# RF-PWR-001.net
KiCad netlist of a schematic drawn in EAGLE
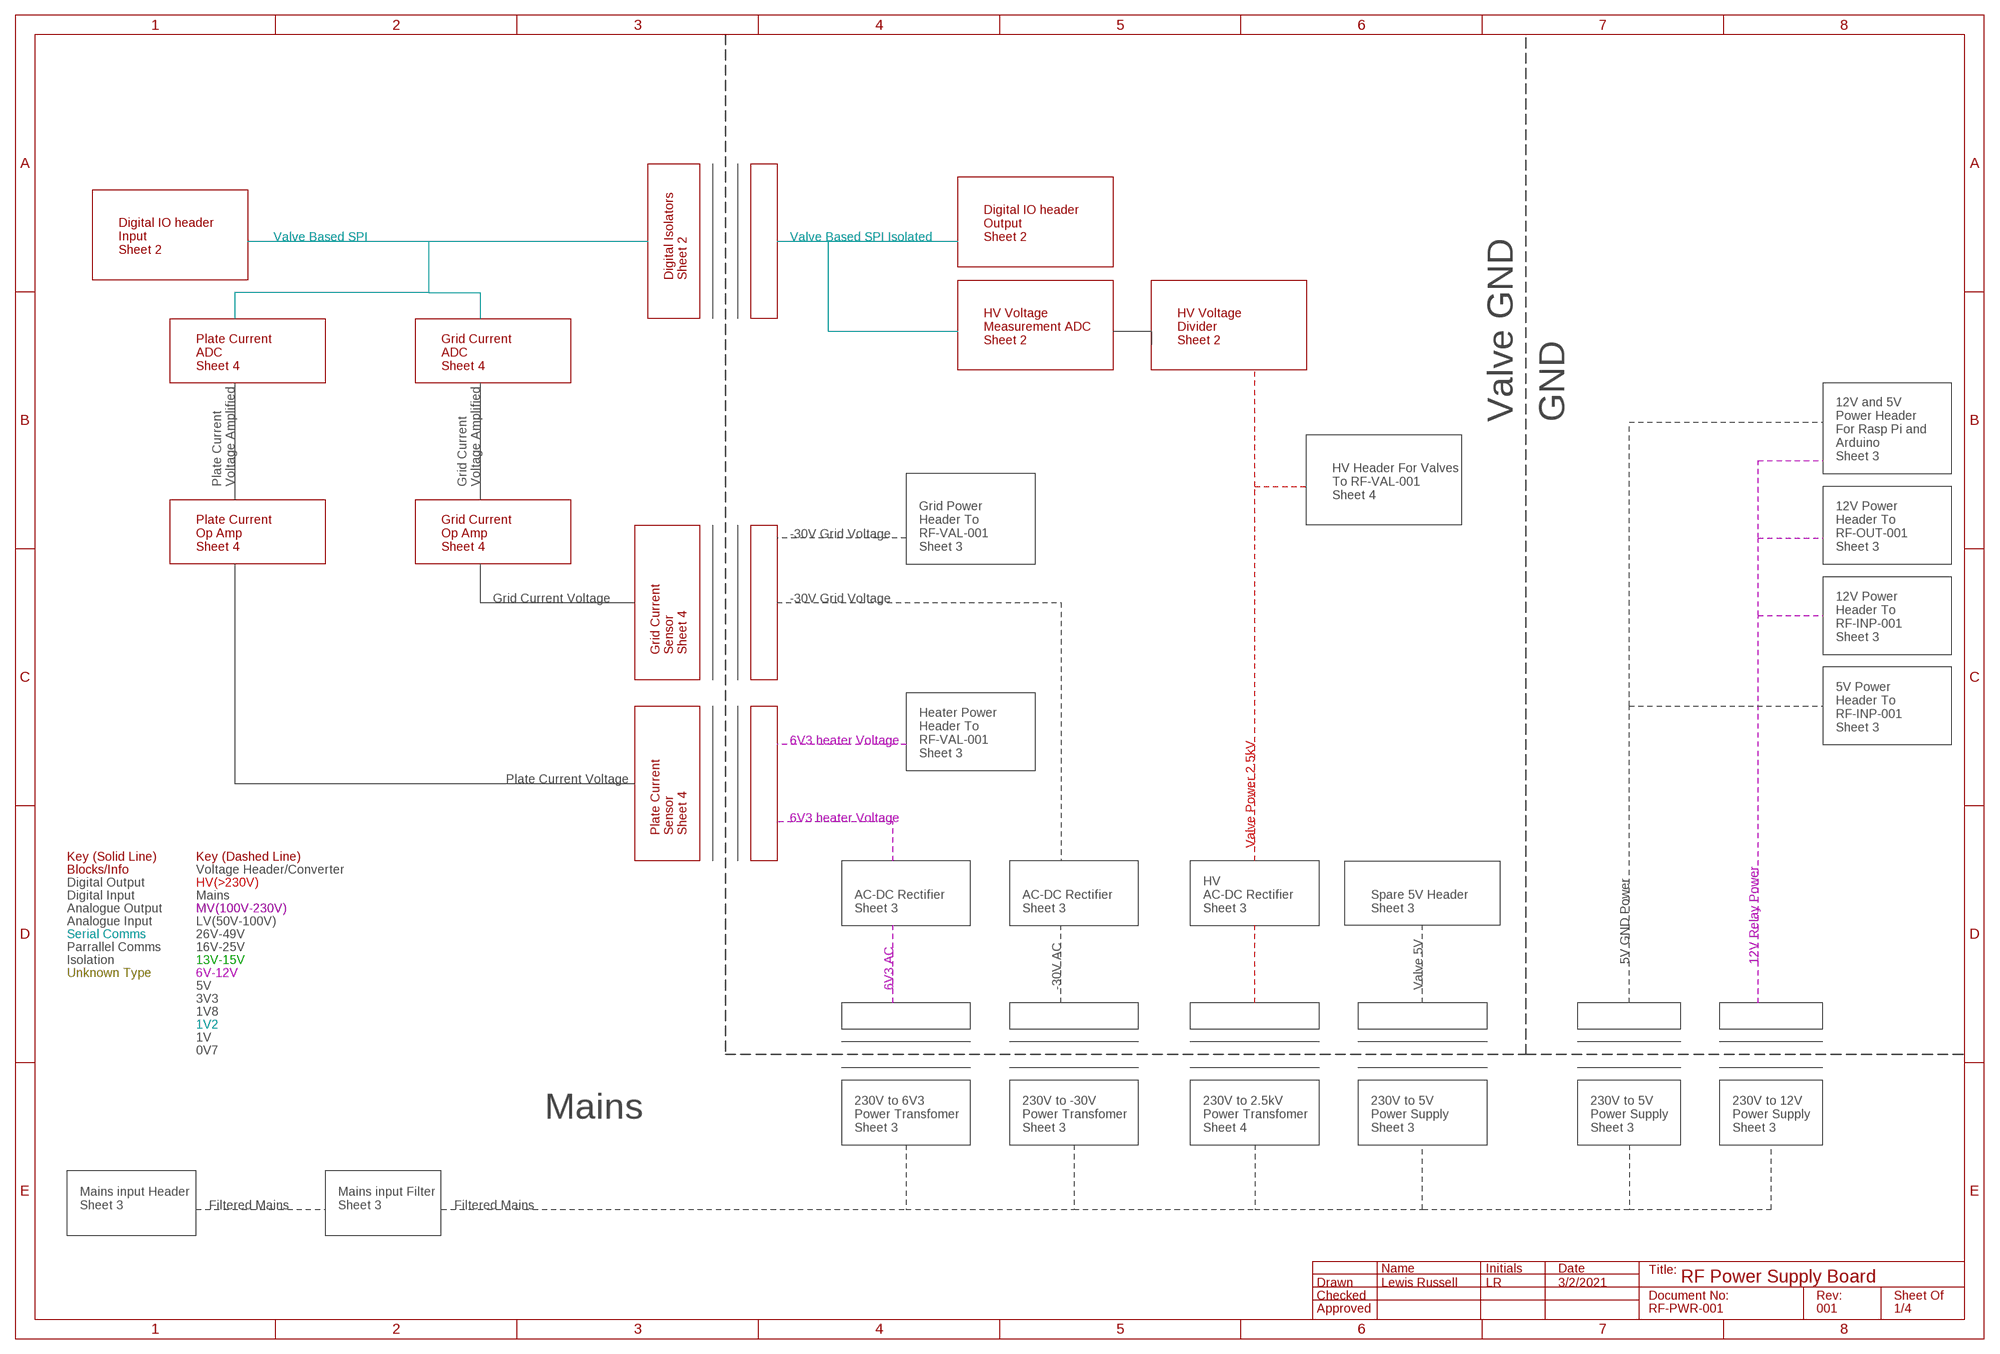
[diagram p0: schematic, sheet 1]
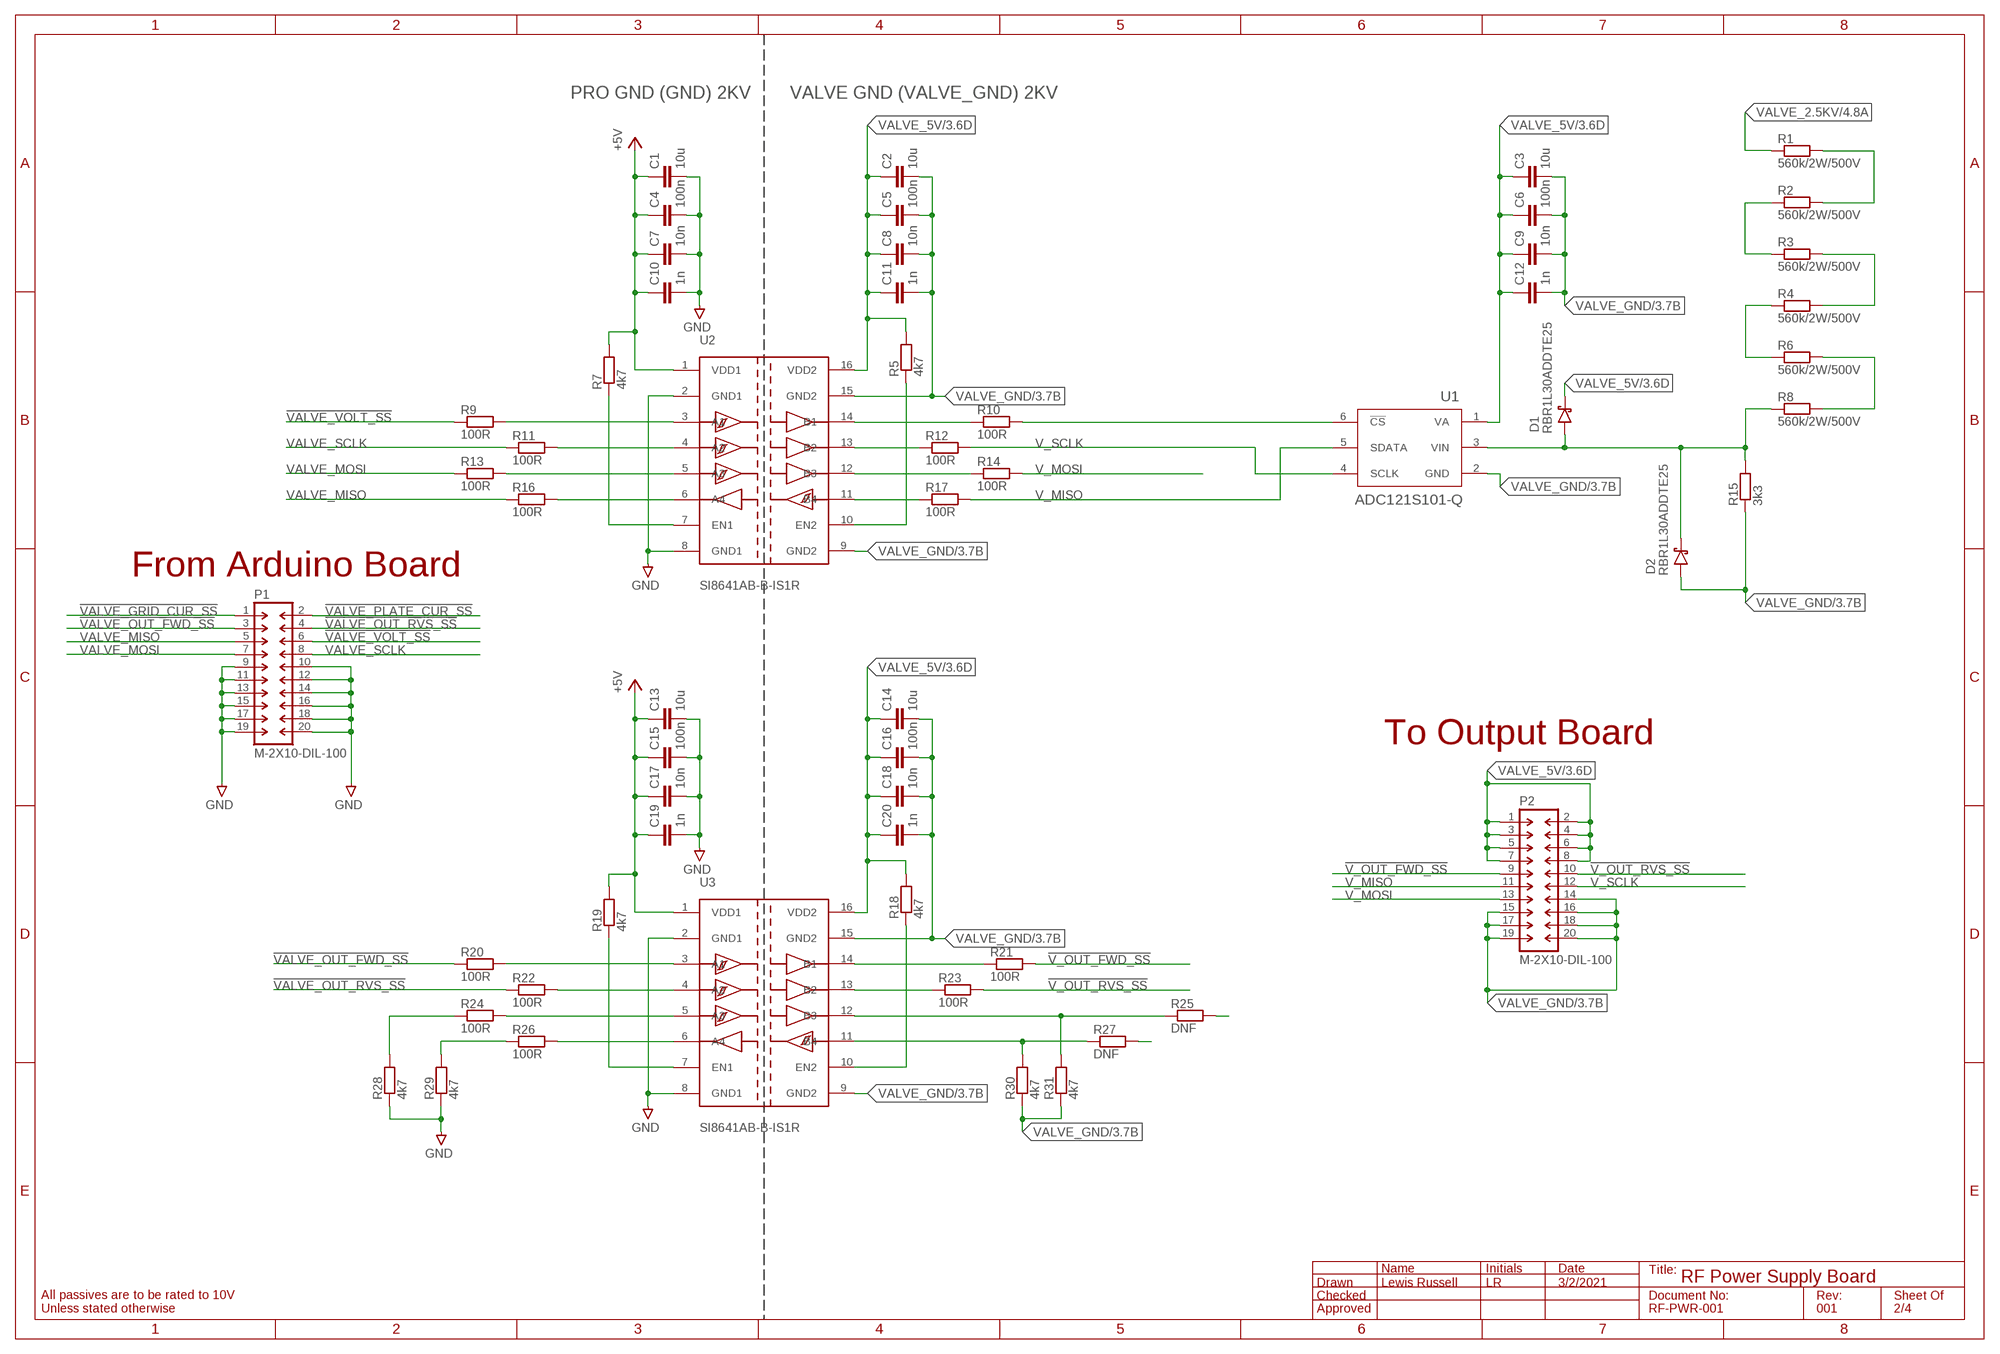
[diagram p1: schematic, sheet 2]
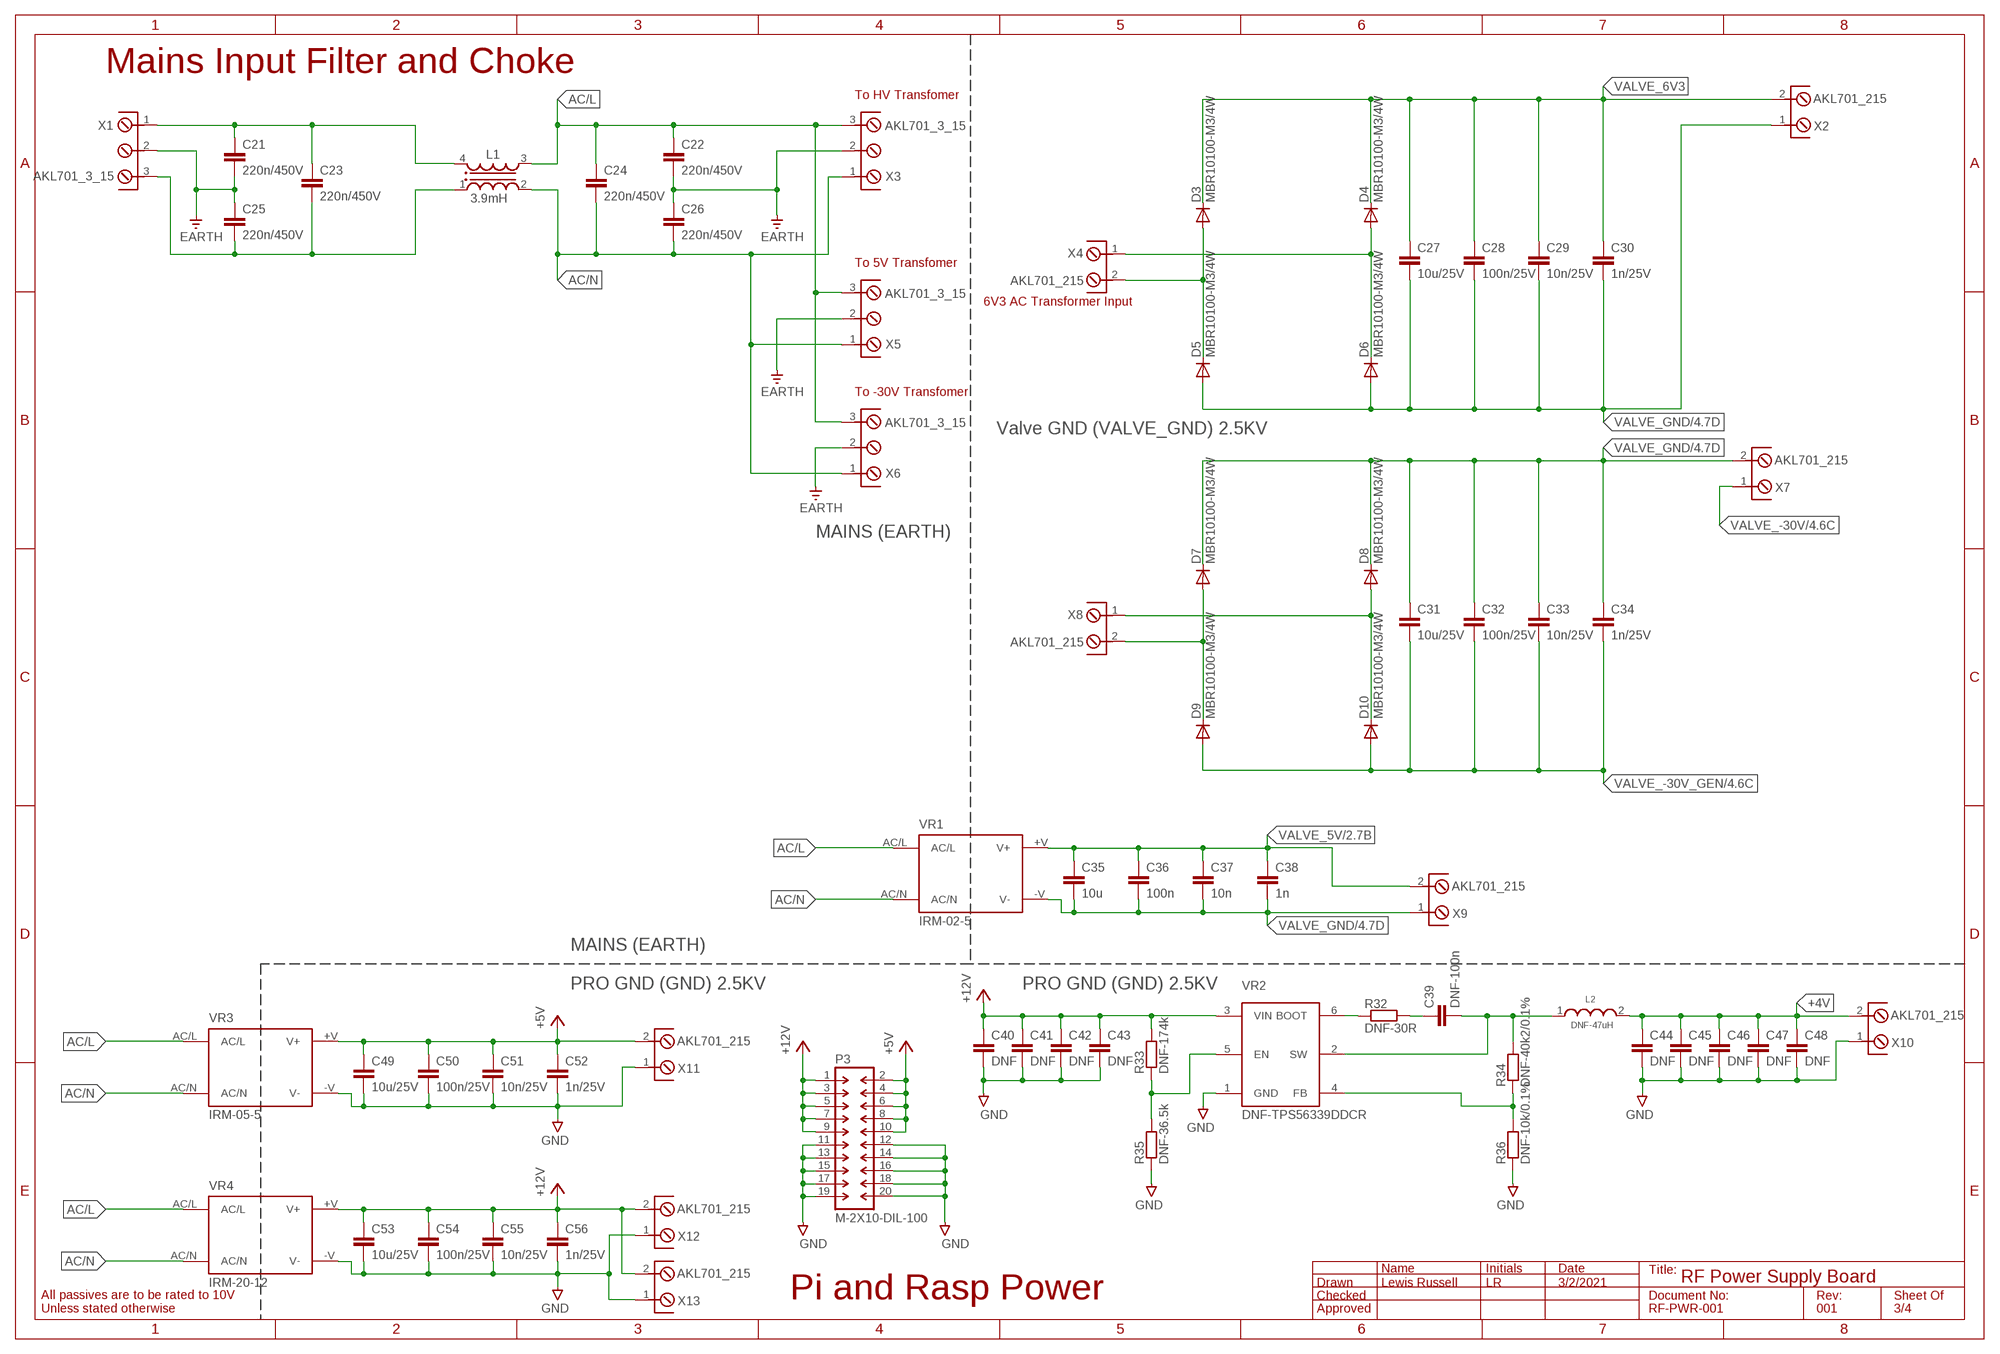
[diagram p2: schematic, sheet 3]
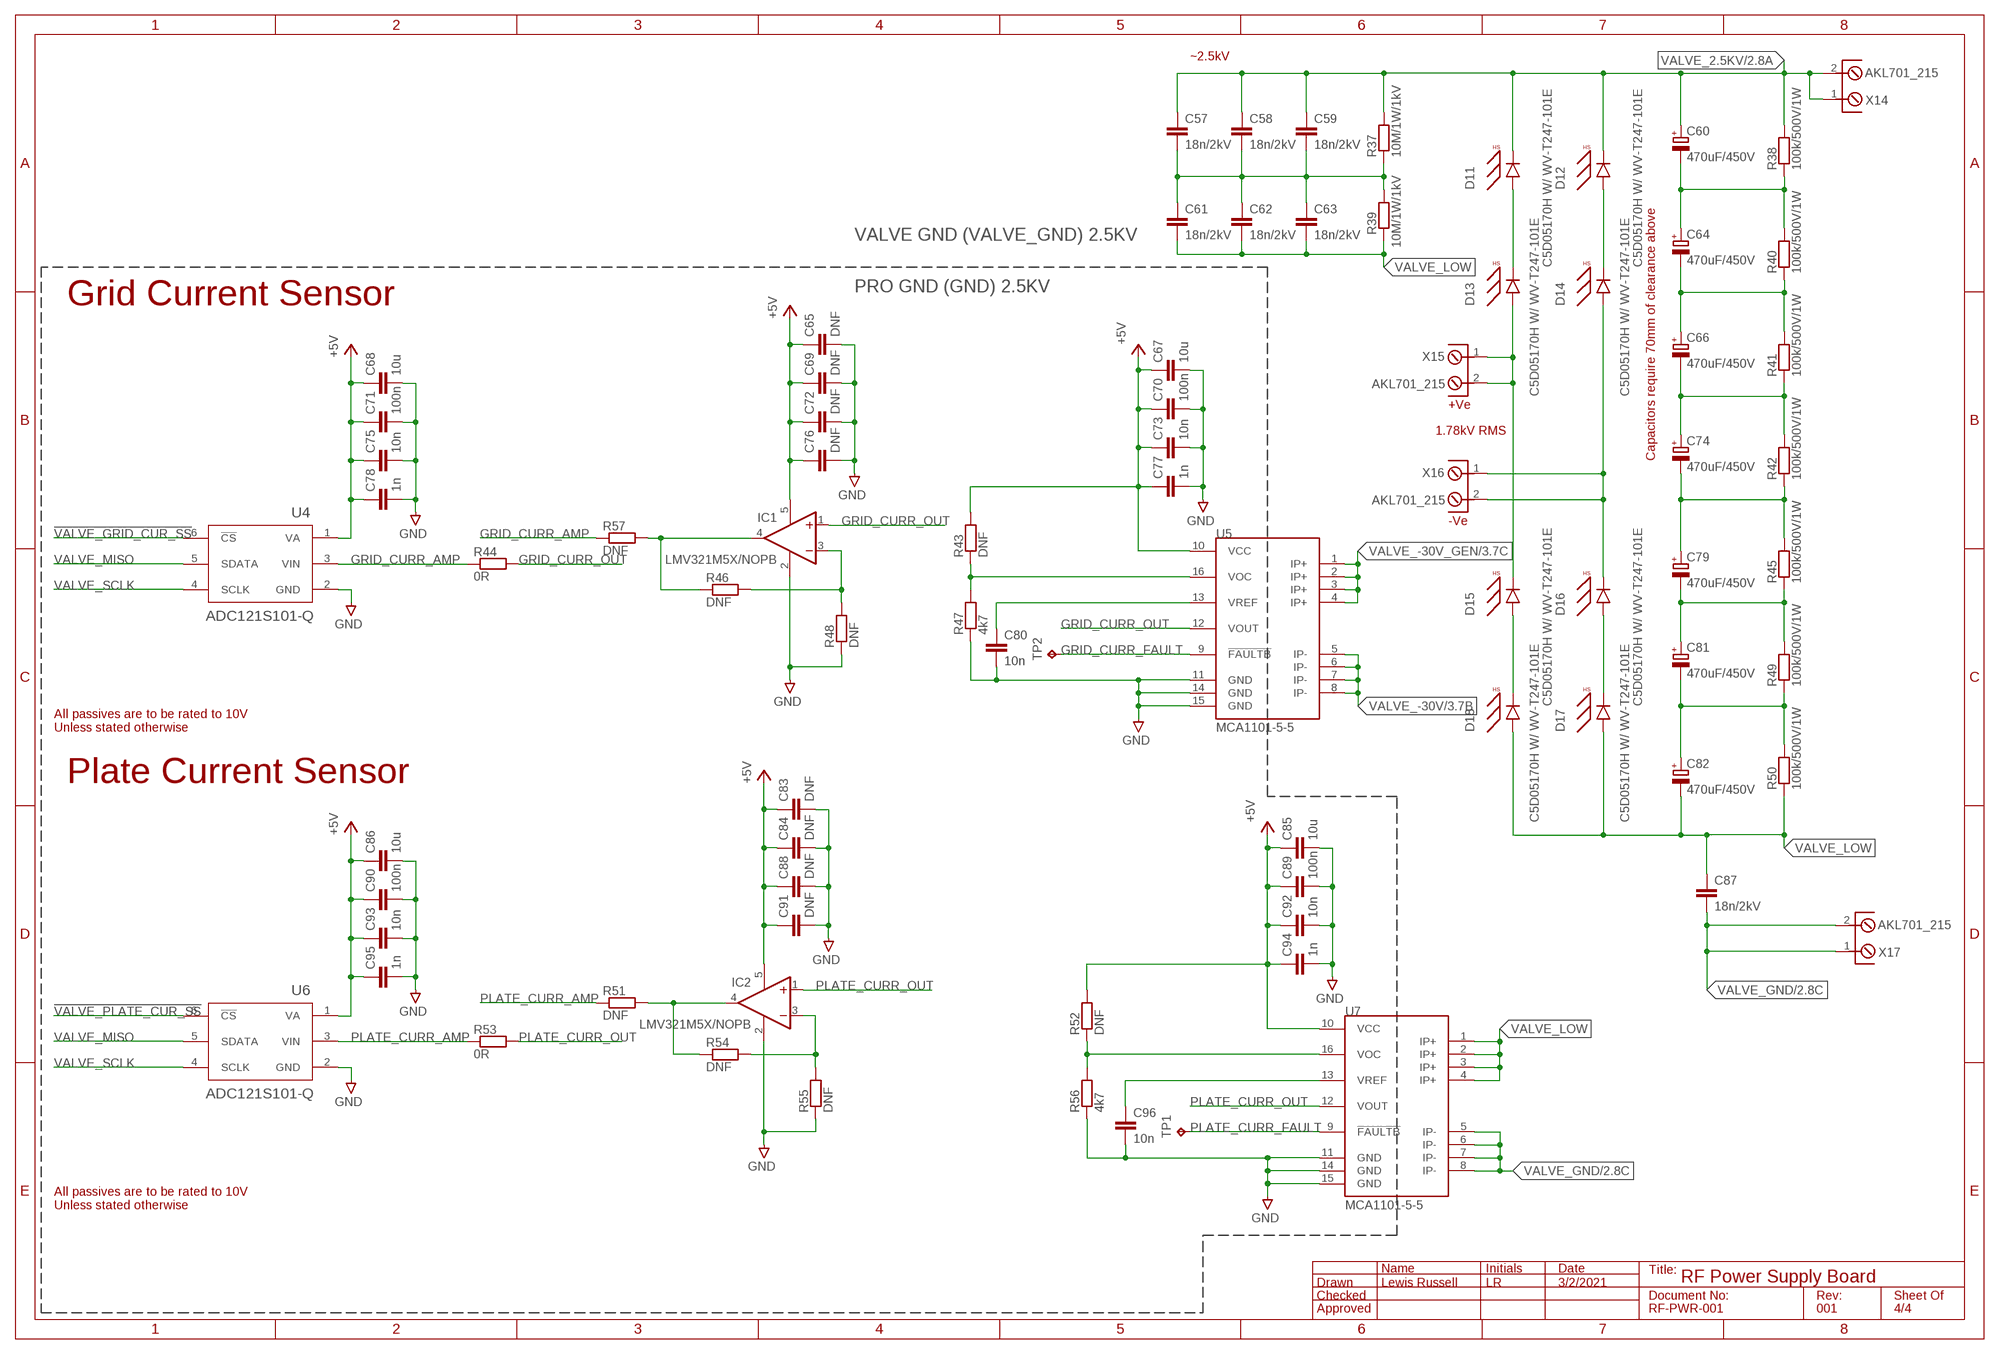
[diagram p3: schematic, sheet 4]

(export (version "E")
  (design (tool "Eeschema 10.0.6"))
  (components
    (comp (ref "C21")
      (value "220n/450V")
      (footprint "eagle-import:C1210")
      (libsource (lib "eagle-import") (part "C-EUC1210"))
    )
    (comp (ref "C22")
      (value "220n/450V")
      (footprint "eagle-import:C1210")
      (libsource (lib "eagle-import") (part "C-EUC1210"))
    )
    (comp (ref "C23")
      (value "220n/450V")
      (footprint "eagle-import:C1210")
      (libsource (lib "eagle-import") (part "C-EUC1210"))
    )
    (comp (ref "C24")
      (value "220n/450V")
      (footprint "eagle-import:C1210")
      (libsource (lib "eagle-import") (part "C-EUC1210"))
    )
    (comp (ref "C25")
      (value "220n/450V")
      (footprint "eagle-import:C1210")
      (libsource (lib "eagle-import") (part "C-EUC1210"))
    )
    (comp (ref "C26")
      (value "220n/450V")
      (footprint "eagle-import:C1210")
      (libsource (lib "eagle-import") (part "C-EUC1210"))
    )
    (comp (ref "C27")
      (value "10u/25V")
      (footprint "eagle-import:C0805")
      (libsource (lib "eagle-import") (part "C-EUC0805"))
    )
    (comp (ref "C28")
      (value "100n/25V")
      (footprint "eagle-import:C0603")
      (libsource (lib "eagle-import") (part "C-EUC0603"))
    )
    (comp (ref "C29")
      (value "10n/25V")
      (footprint "eagle-import:C0603")
      (libsource (lib "eagle-import") (part "C-EUC0603"))
    )
    (comp (ref "C30")
      (value "1n/25V")
      (footprint "eagle-import:C0603")
      (libsource (lib "eagle-import") (part "C-EUC0603"))
    )
    (comp (ref "C31")
      (value "10u/25V")
      (footprint "eagle-import:C0805")
      (libsource (lib "eagle-import") (part "C-EUC0805"))
    )
    (comp (ref "C32")
      (value "100n/25V")
      (footprint "eagle-import:C0603")
      (libsource (lib "eagle-import") (part "C-EUC0603"))
    )
    (comp (ref "C33")
      (value "10n/25V")
      (footprint "eagle-import:C0603")
      (libsource (lib "eagle-import") (part "C-EUC0603"))
    )
    (comp (ref "C34")
      (value "1n/25V")
      (footprint "eagle-import:C0603")
      (libsource (lib "eagle-import") (part "C-EUC0603"))
    )
    (comp (ref "C35")
      (value "10u")
      (footprint "eagle-import:C0805")
      (libsource (lib "eagle-import") (part "C-EUC0805"))
    )
    (comp (ref "C36")
      (value "100n")
      (footprint "eagle-import:C0603")
      (libsource (lib "eagle-import") (part "C-EUC0603"))
    )
    (comp (ref "C37")
      (value "10n")
      (footprint "eagle-import:C0603")
      (libsource (lib "eagle-import") (part "C-EUC0603"))
    )
    (comp (ref "C38")
      (value "1n")
      (footprint "eagle-import:C0603")
      (libsource (lib "eagle-import") (part "C-EUC0603"))
    )
    (comp (ref "C39")
      (value "DNF-100n")
      (footprint "eagle-import:C0603")
      (libsource (lib "eagle-import") (part "C-EUC0603"))
    )
    (comp (ref "C40")
      (value "DNF")
      (footprint "eagle-import:C0805")
      (libsource (lib "eagle-import") (part "C-EUC0805"))
    )
    (comp (ref "C41")
      (value "DNF")
      (footprint "eagle-import:C0603")
      (libsource (lib "eagle-import") (part "C-EUC0603"))
    )
    (comp (ref "C42")
      (value "DNF")
      (footprint "eagle-import:C0603")
      (libsource (lib "eagle-import") (part "C-EUC0603"))
    )
    (comp (ref "C43")
      (value "DNF")
      (footprint "eagle-import:C0603")
      (libsource (lib "eagle-import") (part "C-EUC0603"))
    )
    (comp (ref "C44")
      (value "DNF")
      (footprint "eagle-import:C1206")
      (libsource (lib "eagle-import") (part "C-EUC1206"))
    )
    (comp (ref "C45")
      (value "DNF")
      (footprint "eagle-import:C0805")
      (libsource (lib "eagle-import") (part "C-EUC0805"))
    )
    (comp (ref "C46")
      (value "DNF")
      (footprint "eagle-import:C0603")
      (libsource (lib "eagle-import") (part "C-EUC0603"))
    )
    (comp (ref "C47")
      (value "DNF")
      (footprint "eagle-import:C0603")
      (libsource (lib "eagle-import") (part "C-EUC0603"))
    )
    (comp (ref "C48")
      (value "DNF")
      (footprint "eagle-import:C0603")
      (libsource (lib "eagle-import") (part "C-EUC0603"))
    )
    (comp (ref "C49")
      (value "10u/25V")
      (footprint "eagle-import:C0805")
      (libsource (lib "eagle-import") (part "C-EUC0805"))
    )
    (comp (ref "C50")
      (value "100n/25V")
      (footprint "eagle-import:C0603")
      (libsource (lib "eagle-import") (part "C-EUC0603"))
    )
    (comp (ref "C51")
      (value "10n/25V")
      (footprint "eagle-import:C0603")
      (libsource (lib "eagle-import") (part "C-EUC0603"))
    )
    (comp (ref "C52")
      (value "1n/25V")
      (footprint "eagle-import:C0603")
      (libsource (lib "eagle-import") (part "C-EUC0603"))
    )
    (comp (ref "C53")
      (value "10u/25V")
      (footprint "eagle-import:C0805")
      (libsource (lib "eagle-import") (part "C-EUC0805"))
    )
    (comp (ref "C54")
      (value "100n/25V")
      (footprint "eagle-import:C0603")
      (libsource (lib "eagle-import") (part "C-EUC0603"))
    )
    (comp (ref "C55")
      (value "10n/25V")
      (footprint "eagle-import:C0603")
      (libsource (lib "eagle-import") (part "C-EUC0603"))
    )
    (comp (ref "C56")
      (value "1n/25V")
      (footprint "eagle-import:C0603")
      (libsource (lib "eagle-import") (part "C-EUC0603"))
    )
    (comp (ref "D3")
      (value "MBR10100-M3/4W")
      (footprint "eagle-import:TO220ACS")
      (libsource (lib "eagle-import") (part "DIODE-TO220V"))
    )
    (comp (ref "D4")
      (value "MBR10100-M3/4W")
      (footprint "eagle-import:TO220ACS")
      (libsource (lib "eagle-import") (part "DIODE-TO220V"))
    )
    (comp (ref "D5")
      (value "MBR10100-M3/4W")
      (footprint "eagle-import:TO220ACS")
      (libsource (lib "eagle-import") (part "DIODE-TO220V"))
    )
    (comp (ref "D6")
      (value "MBR10100-M3/4W")
      (footprint "eagle-import:TO220ACS")
      (libsource (lib "eagle-import") (part "DIODE-TO220V"))
    )
    (comp (ref "D7")
      (value "MBR10100-M3/4W")
      (footprint "eagle-import:TO220ACS")
      (libsource (lib "eagle-import") (part "DIODE-TO220V"))
    )
    (comp (ref "D8")
      (value "MBR10100-M3/4W")
      (footprint "eagle-import:TO220ACS")
      (libsource (lib "eagle-import") (part "DIODE-TO220V"))
    )
    (comp (ref "D9")
      (value "MBR10100-M3/4W")
      (footprint "eagle-import:TO220ACS")
      (libsource (lib "eagle-import") (part "DIODE-TO220V"))
    )
    (comp (ref "D10")
      (value "MBR10100-M3/4W")
      (footprint "eagle-import:TO220ACS")
      (libsource (lib "eagle-import") (part "DIODE-TO220V"))
    )
    (comp (ref "L1")
      (value "3.9mH")
      (footprint "eagle-import:WE-FCL_ET35")
      (libsource (lib "eagle-import") (part "WE-FCL_ET35_744866392"))
    )
    (comp (ref "L2")
      (value "DNF-47uH")
      (footprint "eagle-import:WE-HCF_2920_ROUND")
      (libsource (lib "eagle-import") (part "WE-HCF_2920_ROUND_74437529203470"))
    )
    (comp (ref "P3")
      (value "M-2X10-DIL-100")
      (footprint "eagle-import:DIL-100-2X10")
      (libsource (lib "eagle-import") (part "M-2X10-DIL-100"))
    )
    (comp (ref "R32")
      (value "DNF-30R")
      (footprint "eagle-import:R0603")
      (libsource (lib "eagle-import") (part "R-EUR0603"))
    )
    (comp (ref "R33")
      (value "DNF-174k")
      (footprint "eagle-import:R0603")
      (libsource (lib "eagle-import") (part "R-EUR0603"))
    )
    (comp (ref "R34")
      (value "DNF-40k2/0.1%")
      (footprint "eagle-import:R0603")
      (libsource (lib "eagle-import") (part "R-EUR0603"))
    )
    (comp (ref "R35")
      (value "DNF-36.5k")
      (footprint "eagle-import:R0603")
      (libsource (lib "eagle-import") (part "R-EUR0603"))
    )
    (comp (ref "R36")
      (value "DNF-10k/0.1%")
      (footprint "eagle-import:R0603")
      (libsource (lib "eagle-import") (part "R-EUR0603"))
    )
    (comp (ref "VR1")
      (value "IRM-02-5")
      (footprint "eagle-import:IRM_1-2_TH")
      (libsource (lib "eagle-import") (part "IRM-02-5"))
    )
    (comp (ref "VR2")
      (value "DNF-TPS56339DDCR")
      (footprint "eagle-import:SOT23-6")
      (libsource (lib "eagle-import") (part "TPS56339DDCR"))
    )
    (comp (ref "VR3")
      (value "IRM-05-5")
      (footprint "eagle-import:IRM_5-10_TH")
      (libsource (lib "eagle-import") (part "IRM-05-5"))
    )
    (comp (ref "VR4")
      (value "IRM-20-12")
      (footprint "eagle-import:IRM_15-20_TH")
      (libsource (lib "eagle-import") (part "IRM-20-12"))
    )
    (comp (ref "X1")
      (value "AKL701_3_15")
      (footprint "eagle-import:AKL701_3_15")
      (libsource (lib "eagle-import") (part "AKL701_3_15"))
    )
    (comp (ref "X2")
      (value "AKL701_215")
      (footprint "eagle-import:AKL701_2_15")
      (libsource (lib "eagle-import") (part "AKL701_215"))
    )
    (comp (ref "X3")
      (value "AKL701_3_15")
      (footprint "eagle-import:AKL701_3_15")
      (libsource (lib "eagle-import") (part "AKL701_3_15"))
    )
    (comp (ref "X4")
      (value "AKL701_215")
      (footprint "eagle-import:AKL701_2_15")
      (libsource (lib "eagle-import") (part "AKL701_215"))
    )
    (comp (ref "X5")
      (value "AKL701_3_15")
      (footprint "eagle-import:AKL701_3_15")
      (libsource (lib "eagle-import") (part "AKL701_3_15"))
    )
    (comp (ref "X6")
      (value "AKL701_3_15")
      (footprint "eagle-import:AKL701_3_15")
      (libsource (lib "eagle-import") (part "AKL701_3_15"))
    )
    (comp (ref "X7")
      (value "AKL701_215")
      (footprint "eagle-import:AKL701_2_15")
      (libsource (lib "eagle-import") (part "AKL701_215"))
    )
    (comp (ref "X8")
      (value "AKL701_215")
      (footprint "eagle-import:AKL701_2_15")
      (libsource (lib "eagle-import") (part "AKL701_215"))
    )
    (comp (ref "X9")
      (value "AKL701_215")
      (footprint "eagle-import:AKL701_2_15")
      (libsource (lib "eagle-import") (part "AKL701_215"))
    )
    (comp (ref "X10")
      (value "AKL701_215")
      (footprint "eagle-import:AKL701_2_15")
      (libsource (lib "eagle-import") (part "AKL701_215"))
    )
    (comp (ref "X11")
      (value "AKL701_215")
      (footprint "eagle-import:AKL701_2_15")
      (libsource (lib "eagle-import") (part "AKL701_215"))
    )
    (comp (ref "X12")
      (value "AKL701_215")
      (footprint "eagle-import:AKL701_2_15")
      (libsource (lib "eagle-import") (part "AKL701_215"))
    )
    (comp (ref "X13")
      (value "AKL701_215")
      (footprint "eagle-import:AKL701_2_15")
      (libsource (lib "eagle-import") (part "AKL701_215"))
    )
    (comp (ref "C57")
      (value "18n/2kV")
      (footprint "eagle-import:C050-075X075")
      (libsource (lib "eagle-import") (part "C-EU050-075X075"))
    )
    (comp (ref "C58")
      (value "18n/2kV")
      (footprint "eagle-import:C050-075X075")
      (libsource (lib "eagle-import") (part "C-EU050-075X075"))
    )
    (comp (ref "C59")
      (value "18n/2kV")
      (footprint "eagle-import:C050-075X075")
      (libsource (lib "eagle-import") (part "C-EU050-075X075"))
    )
    (comp (ref "C60")
      (value "470uF/450V")
      (footprint "eagle-import:STYLE_D(35MM)")
      (libsource (lib "eagle-import") (part "ALC10D-35MM"))
    )
    (comp (ref "C61")
      (value "18n/2kV")
      (footprint "eagle-import:C050-075X075")
      (libsource (lib "eagle-import") (part "C-EU050-075X075"))
    )
    (comp (ref "C62")
      (value "18n/2kV")
      (footprint "eagle-import:C050-075X075")
      (libsource (lib "eagle-import") (part "C-EU050-075X075"))
    )
    (comp (ref "C63")
      (value "18n/2kV")
      (footprint "eagle-import:C050-075X075")
      (libsource (lib "eagle-import") (part "C-EU050-075X075"))
    )
    (comp (ref "C64")
      (value "470uF/450V")
      (footprint "eagle-import:STYLE_D(35MM)")
      (libsource (lib "eagle-import") (part "ALC10D-35MM"))
    )
    (comp (ref "C65")
      (value "DNF")
      (footprint "eagle-import:C0805")
      (libsource (lib "eagle-import") (part "C-EUC0805"))
    )
    (comp (ref "C66")
      (value "470uF/450V")
      (footprint "eagle-import:STYLE_D(35MM)")
      (libsource (lib "eagle-import") (part "ALC10D-35MM"))
    )
    (comp (ref "C67")
      (value "10u")
      (footprint "eagle-import:C0805")
      (libsource (lib "eagle-import") (part "C-EUC0805"))
    )
    (comp (ref "C68")
      (value "10u")
      (footprint "eagle-import:C0805")
      (libsource (lib "eagle-import") (part "C-EUC0805"))
    )
    (comp (ref "C69")
      (value "DNF")
      (footprint "eagle-import:C0603")
      (libsource (lib "eagle-import") (part "C-EUC0603"))
    )
    (comp (ref "C70")
      (value "100n")
      (footprint "eagle-import:C0603")
      (libsource (lib "eagle-import") (part "C-EUC0603"))
    )
    (comp (ref "C71")
      (value "100n")
      (footprint "eagle-import:C0603")
      (libsource (lib "eagle-import") (part "C-EUC0603"))
    )
    (comp (ref "C72")
      (value "DNF")
      (footprint "eagle-import:C0603")
      (libsource (lib "eagle-import") (part "C-EUC0603"))
    )
    (comp (ref "C73")
      (value "10n")
      (footprint "eagle-import:C0603")
      (libsource (lib "eagle-import") (part "C-EUC0603"))
    )
    (comp (ref "C74")
      (value "470uF/450V")
      (footprint "eagle-import:STYLE_D(35MM)")
      (libsource (lib "eagle-import") (part "ALC10D-35MM"))
    )
    (comp (ref "C75")
      (value "10n")
      (footprint "eagle-import:C0603")
      (libsource (lib "eagle-import") (part "C-EUC0603"))
    )
    (comp (ref "C76")
      (value "DNF")
      (footprint "eagle-import:C0603")
      (libsource (lib "eagle-import") (part "C-EUC0603"))
    )
    (comp (ref "C77")
      (value "1n")
      (footprint "eagle-import:C0603")
      (libsource (lib "eagle-import") (part "C-EUC0603"))
    )
    (comp (ref "C78")
      (value "1n")
      (footprint "eagle-import:C0603")
      (libsource (lib "eagle-import") (part "C-EUC0603"))
    )
    (comp (ref "C79")
      (value "470uF/450V")
      (footprint "eagle-import:STYLE_D(35MM)")
      (libsource (lib "eagle-import") (part "ALC10D-35MM"))
    )
    (comp (ref "C80")
      (value "10n")
      (footprint "eagle-import:C0603")
      (libsource (lib "eagle-import") (part "C-EUC0603"))
    )
    (comp (ref "C81")
      (value "470uF/450V")
      (footprint "eagle-import:STYLE_D(35MM)")
      (libsource (lib "eagle-import") (part "ALC10D-35MM"))
    )
    (comp (ref "C82")
      (value "470uF/450V")
      (footprint "eagle-import:STYLE_D(35MM)")
      (libsource (lib "eagle-import") (part "ALC10D-35MM"))
    )
    (comp (ref "C83")
      (value "DNF")
      (footprint "eagle-import:C0805")
      (libsource (lib "eagle-import") (part "C-EUC0805"))
    )
    (comp (ref "C84")
      (value "DNF")
      (footprint "eagle-import:C0603")
      (libsource (lib "eagle-import") (part "C-EUC0603"))
    )
    (comp (ref "C85")
      (value "10u")
      (footprint "eagle-import:C0805")
      (libsource (lib "eagle-import") (part "C-EUC0805"))
    )
    (comp (ref "C86")
      (value "10u")
      (footprint "eagle-import:C0805")
      (libsource (lib "eagle-import") (part "C-EUC0805"))
    )
    (comp (ref "C87")
      (value "18n/2kV")
      (footprint "eagle-import:C050-075X075")
      (libsource (lib "eagle-import") (part "C-EU050-075X075"))
    )
    (comp (ref "C88")
      (value "DNF")
      (footprint "eagle-import:C0603")
      (libsource (lib "eagle-import") (part "C-EUC0603"))
    )
    (comp (ref "C89")
      (value "100n")
      (footprint "eagle-import:C0603")
      (libsource (lib "eagle-import") (part "C-EUC0603"))
    )
    (comp (ref "C90")
      (value "100n")
      (footprint "eagle-import:C0603")
      (libsource (lib "eagle-import") (part "C-EUC0603"))
    )
    (comp (ref "C91")
      (value "DNF")
      (footprint "eagle-import:C0603")
      (libsource (lib "eagle-import") (part "C-EUC0603"))
    )
    (comp (ref "C92")
      (value "10n")
      (footprint "eagle-import:C0603")
      (libsource (lib "eagle-import") (part "C-EUC0603"))
    )
    (comp (ref "C93")
      (value "10n")
      (footprint "eagle-import:C0603")
      (libsource (lib "eagle-import") (part "C-EUC0603"))
    )
    (comp (ref "C94")
      (value "1n")
      (footprint "eagle-import:C0603")
      (libsource (lib "eagle-import") (part "C-EUC0603"))
    )
    (comp (ref "C95")
      (value "1n")
      (footprint "eagle-import:C0603")
      (libsource (lib "eagle-import") (part "C-EUC0603"))
    )
    (comp (ref "C96")
      (value "10n")
      (footprint "eagle-import:C0603")
      (libsource (lib "eagle-import") (part "C-EUC0603"))
    )
    (comp (ref "D11")
      (value "C5D05170H W/ WV-T247-101E")
      (footprint "eagle-import:TO-247-2-WA-T247-101E")
      (libsource (lib "eagle-import") (part "DIODE_WITH_HEATSINKC3A1-2"))
    )
    (comp (ref "D12")
      (value "C5D05170H W/ WV-T247-101E")
      (footprint "eagle-import:TO-247-2-WA-T247-101E")
      (libsource (lib "eagle-import") (part "DIODE_WITH_HEATSINKC3A1-2"))
    )
    (comp (ref "D13")
      (value "C5D05170H W/ WV-T247-101E")
      (footprint "eagle-import:TO-247-2-WA-T247-101E")
      (libsource (lib "eagle-import") (part "DIODE_WITH_HEATSINKC3A1-2"))
    )
    (comp (ref "D14")
      (value "C5D05170H W/ WV-T247-101E")
      (footprint "eagle-import:TO-247-2-WA-T247-101E")
      (libsource (lib "eagle-import") (part "DIODE_WITH_HEATSINKC3A1-2"))
    )
    (comp (ref "D15")
      (value "C5D05170H W/ WV-T247-101E")
      (footprint "eagle-import:TO-247-2-WA-T247-101E")
      (libsource (lib "eagle-import") (part "DIODE_WITH_HEATSINKC3A1-2"))
    )
    (comp (ref "D16")
      (value "C5D05170H W/ WV-T247-101E")
      (footprint "eagle-import:TO-247-2-WA-T247-101E")
      (libsource (lib "eagle-import") (part "DIODE_WITH_HEATSINKC3A1-2"))
    )
    (comp (ref "D17")
      (value "C5D05170H W/ WV-T247-101E")
      (footprint "eagle-import:TO-247-2-WA-T247-101E")
      (libsource (lib "eagle-import") (part "DIODE_WITH_HEATSINKC3A1-2"))
    )
    (comp (ref "D18")
      (value "C5D05170H W/ WV-T247-101E")
      (footprint "eagle-import:TO-247-2-WA-T247-101E")
      (libsource (lib "eagle-import") (part "DIODE_WITH_HEATSINKC3A1-2"))
    )
    (comp (ref "IC1")
      (value "LMV321M5X/NOPB")
      (footprint "eagle-import:SOT23-5")
      (libsource (lib "eagle-import") (part "LMV321?M5"))
    )
    (comp (ref "IC2")
      (value "LMV321M5X/NOPB")
      (footprint "eagle-import:SOT23-5")
      (libsource (lib "eagle-import") (part "LMV321?M5"))
    )
    (comp (ref "R37")
      (value "10M/1W/1kV")
      (footprint "eagle-import:R2512")
      (libsource (lib "eagle-import") (part "R-EUR2512"))
    )
    (comp (ref "R38")
      (value "100k/500V/1W")
      (footprint "eagle-import:R2512")
      (libsource (lib "eagle-import") (part "R-EUR2512"))
    )
    (comp (ref "R39")
      (value "10M/1W/1kV")
      (footprint "eagle-import:R2512")
      (libsource (lib "eagle-import") (part "R-EUR2512"))
    )
    (comp (ref "R40")
      (value "100k/500V/1W")
      (footprint "eagle-import:R2512")
      (libsource (lib "eagle-import") (part "R-EUR2512"))
    )
    (comp (ref "R41")
      (value "100k/500V/1W")
      (footprint "eagle-import:R2512")
      (libsource (lib "eagle-import") (part "R-EUR2512"))
    )
    (comp (ref "R42")
      (value "100k/500V/1W")
      (footprint "eagle-import:R2512")
      (libsource (lib "eagle-import") (part "R-EUR2512"))
    )
    (comp (ref "R43")
      (value "DNF")
      (footprint "eagle-import:R0603")
      (libsource (lib "eagle-import") (part "R-EUR0603"))
    )
    (comp (ref "R44")
      (value "0R")
      (footprint "eagle-import:R0603")
      (libsource (lib "eagle-import") (part "R-EUR0603"))
    )
    (comp (ref "R45")
      (value "100k/500V/1W")
      (footprint "eagle-import:R2512")
      (libsource (lib "eagle-import") (part "R-EUR2512"))
    )
    (comp (ref "R46")
      (value "DNF")
      (footprint "eagle-import:R0603")
      (libsource (lib "eagle-import") (part "R-EUR0603"))
    )
    (comp (ref "R47")
      (value "4k7")
      (footprint "eagle-import:R0603")
      (libsource (lib "eagle-import") (part "R-EUR0603"))
    )
    (comp (ref "R48")
      (value "DNF")
      (footprint "eagle-import:R0603")
      (libsource (lib "eagle-import") (part "R-EUR0603"))
    )
    (comp (ref "R49")
      (value "100k/500V/1W")
      (footprint "eagle-import:R2512")
      (libsource (lib "eagle-import") (part "R-EUR2512"))
    )
    (comp (ref "R50")
      (value "100k/500V/1W")
      (footprint "eagle-import:R2512")
      (libsource (lib "eagle-import") (part "R-EUR2512"))
    )
    (comp (ref "R51")
      (value "DNF")
      (footprint "eagle-import:R0603")
      (libsource (lib "eagle-import") (part "R-EUR0603"))
    )
    (comp (ref "R52")
      (value "DNF")
      (footprint "eagle-import:R0603")
      (libsource (lib "eagle-import") (part "R-EUR0603"))
    )
    (comp (ref "R53")
      (value "0R")
      (footprint "eagle-import:R0603")
      (libsource (lib "eagle-import") (part "R-EUR0603"))
    )
    (comp (ref "R54")
      (value "DNF")
      (footprint "eagle-import:R0603")
      (libsource (lib "eagle-import") (part "R-EUR0603"))
    )
    (comp (ref "R55")
      (value "DNF")
      (footprint "eagle-import:R0603")
      (libsource (lib "eagle-import") (part "R-EUR0603"))
    )
    (comp (ref "R56")
      (value "4k7")
      (footprint "eagle-import:R0603")
      (libsource (lib "eagle-import") (part "R-EUR0603"))
    )
    (comp (ref "R57")
      (value "DNF")
      (footprint "eagle-import:R0603")
      (libsource (lib "eagle-import") (part "R-EUR0603"))
    )
    (comp (ref "TP1")
      (value "TPTP16R")
      (footprint "eagle-import:TP16R")
      (libsource (lib "eagle-import") (part "TPTP16R"))
    )
    (comp (ref "TP2")
      (value "TPTP16R")
      (footprint "eagle-import:TP16R")
      (libsource (lib "eagle-import") (part "TPTP16R"))
    )
    (comp (ref "U4")
      (value "ADC121S101-Q")
      (footprint "eagle-import:SOT23-6")
      (libsource (lib "eagle-import") (part "ADC121S101-Q"))
    )
    (comp (ref "U5")
      (value "MCA1101-5-5")
      (footprint "eagle-import:SOIC_16")
      (libsource (lib "eagle-import") (part "MCA1101-5-5"))
    )
    (comp (ref "U6")
      (value "ADC121S101-Q")
      (footprint "eagle-import:SOT23-6")
      (libsource (lib "eagle-import") (part "ADC121S101-Q"))
    )
    (comp (ref "U7")
      (value "MCA1101-5-5")
      (footprint "eagle-import:SOIC_16")
      (libsource (lib "eagle-import") (part "MCA1101-5-5"))
    )
    (comp (ref "X14")
      (value "AKL701_215")
      (footprint "eagle-import:AKL701_2_15")
      (libsource (lib "eagle-import") (part "AKL701_215"))
    )
    (comp (ref "X15")
      (value "AKL701_215")
      (footprint "eagle-import:AKL701_2_15")
      (libsource (lib "eagle-import") (part "AKL701_215"))
    )
    (comp (ref "X16")
      (value "AKL701_215")
      (footprint "eagle-import:AKL701_2_15")
      (libsource (lib "eagle-import") (part "AKL701_215"))
    )
    (comp (ref "X17")
      (value "AKL701_215")
      (footprint "eagle-import:AKL701_2_15")
      (libsource (lib "eagle-import") (part "AKL701_215"))
    )
    (comp (ref "C1")
      (value "10u")
      (footprint "eagle-import:C0805")
      (libsource (lib "eagle-import") (part "C-EUC0805"))
    )
    (comp (ref "C2")
      (value "10u")
      (footprint "eagle-import:C0805")
      (libsource (lib "eagle-import") (part "C-EUC0805"))
    )
    (comp (ref "C3")
      (value "10u")
      (footprint "eagle-import:C0805")
      (libsource (lib "eagle-import") (part "C-EUC0805"))
    )
    (comp (ref "C4")
      (value "100n")
      (footprint "eagle-import:C0603")
      (libsource (lib "eagle-import") (part "C-EUC0603"))
    )
    (comp (ref "C5")
      (value "100n")
      (footprint "eagle-import:C0603")
      (libsource (lib "eagle-import") (part "C-EUC0603"))
    )
    (comp (ref "C6")
      (value "100n")
      (footprint "eagle-import:C0603")
      (libsource (lib "eagle-import") (part "C-EUC0603"))
    )
    (comp (ref "C7")
      (value "10n")
      (footprint "eagle-import:C0603")
      (libsource (lib "eagle-import") (part "C-EUC0603"))
    )
    (comp (ref "C8")
      (value "10n")
      (footprint "eagle-import:C0603")
      (libsource (lib "eagle-import") (part "C-EUC0603"))
    )
    (comp (ref "C9")
      (value "10n")
      (footprint "eagle-import:C0603")
      (libsource (lib "eagle-import") (part "C-EUC0603"))
    )
    (comp (ref "C10")
      (value "1n")
      (footprint "eagle-import:C0603")
      (libsource (lib "eagle-import") (part "C-EUC0603"))
    )
    (comp (ref "C11")
      (value "1n")
      (footprint "eagle-import:C0603")
      (libsource (lib "eagle-import") (part "C-EUC0603"))
    )
    (comp (ref "C12")
      (value "1n")
      (footprint "eagle-import:C0603")
      (libsource (lib "eagle-import") (part "C-EUC0603"))
    )
    (comp (ref "C13")
      (value "10u")
      (footprint "eagle-import:C0805")
      (libsource (lib "eagle-import") (part "C-EUC0805"))
    )
    (comp (ref "C14")
      (value "10u")
      (footprint "eagle-import:C0805")
      (libsource (lib "eagle-import") (part "C-EUC0805"))
    )
    (comp (ref "C15")
      (value "100n")
      (footprint "eagle-import:C0603")
      (libsource (lib "eagle-import") (part "C-EUC0603"))
    )
    (comp (ref "C16")
      (value "100n")
      (footprint "eagle-import:C0603")
      (libsource (lib "eagle-import") (part "C-EUC0603"))
    )
    (comp (ref "C17")
      (value "10n")
      (footprint "eagle-import:C0603")
      (libsource (lib "eagle-import") (part "C-EUC0603"))
    )
    (comp (ref "C18")
      (value "10n")
      (footprint "eagle-import:C0603")
      (libsource (lib "eagle-import") (part "C-EUC0603"))
    )
    (comp (ref "C19")
      (value "1n")
      (footprint "eagle-import:C0603")
      (libsource (lib "eagle-import") (part "C-EUC0603"))
    )
    (comp (ref "C20")
      (value "1n")
      (footprint "eagle-import:C0603")
      (libsource (lib "eagle-import") (part "C-EUC0603"))
    )
    (comp (ref "D1")
      (value "RBR1L30ADDTE25")
      (footprint "eagle-import:SMA_DO-214AC")
      (libsource (lib "eagle-import") (part "SCHOTTKY_DIODESMA"))
    )
    (comp (ref "D2")
      (value "RBR1L30ADDTE25")
      (footprint "eagle-import:SMA_DO-214AC")
      (libsource (lib "eagle-import") (part "SCHOTTKY_DIODESMA"))
    )
    (comp (ref "P1")
      (value "M-2X10-DIL-100")
      (footprint "eagle-import:DIL-100-2X10")
      (libsource (lib "eagle-import") (part "M-2X10-DIL-100"))
    )
    (comp (ref "P2")
      (value "M-2X10-DIL-100")
      (footprint "eagle-import:DIL-100-2X10")
      (libsource (lib "eagle-import") (part "M-2X10-DIL-100"))
    )
    (comp (ref "R1")
      (value "560k/2W/500V")
      (footprint "eagle-import:SMV1_SMF2")
      (libsource (lib "eagle-import") (part "R-EU_SMF2"))
    )
    (comp (ref "R2")
      (value "560k/2W/500V")
      (footprint "eagle-import:SMV1_SMF2")
      (libsource (lib "eagle-import") (part "R-EU_SMF2"))
    )
    (comp (ref "R3")
      (value "560k/2W/500V")
      (footprint "eagle-import:SMV1_SMF2")
      (libsource (lib "eagle-import") (part "R-EU_SMF2"))
    )
    (comp (ref "R4")
      (value "560k/2W/500V")
      (footprint "eagle-import:SMV1_SMF2")
      (libsource (lib "eagle-import") (part "R-EU_SMF2"))
    )
    (comp (ref "R5")
      (value "4k7")
      (footprint "eagle-import:R0603")
      (libsource (lib "eagle-import") (part "R-EUR0603"))
    )
    (comp (ref "R6")
      (value "560k/2W/500V")
      (footprint "eagle-import:SMV1_SMF2")
      (libsource (lib "eagle-import") (part "R-EU_SMF2"))
    )
    (comp (ref "R7")
      (value "4k7")
      (footprint "eagle-import:R0603")
      (libsource (lib "eagle-import") (part "R-EUR0603"))
    )
    (comp (ref "R8")
      (value "560k/2W/500V")
      (footprint "eagle-import:SMV1_SMF2")
      (libsource (lib "eagle-import") (part "R-EU_SMF2"))
    )
    (comp (ref "R9")
      (value "100R")
      (footprint "eagle-import:R0603")
      (libsource (lib "eagle-import") (part "R-EUR0603"))
    )
    (comp (ref "R10")
      (value "100R")
      (footprint "eagle-import:R0603")
      (libsource (lib "eagle-import") (part "R-EUR0603"))
    )
    (comp (ref "R11")
      (value "100R")
      (footprint "eagle-import:R0603")
      (libsource (lib "eagle-import") (part "R-EUR0603"))
    )
    (comp (ref "R12")
      (value "100R")
      (footprint "eagle-import:R0603")
      (libsource (lib "eagle-import") (part "R-EUR0603"))
    )
    (comp (ref "R13")
      (value "100R")
      (footprint "eagle-import:R0603")
      (libsource (lib "eagle-import") (part "R-EUR0603"))
    )
    (comp (ref "R14")
      (value "100R")
      (footprint "eagle-import:R0603")
      (libsource (lib "eagle-import") (part "R-EUR0603"))
    )
    (comp (ref "R15")
      (value "3k3")
      (footprint "eagle-import:R0603")
      (libsource (lib "eagle-import") (part "R-EUR0603"))
    )
    (comp (ref "R16")
      (value "100R")
      (footprint "eagle-import:R0603")
      (libsource (lib "eagle-import") (part "R-EUR0603"))
    )
    (comp (ref "R17")
      (value "100R")
      (footprint "eagle-import:R0603")
      (libsource (lib "eagle-import") (part "R-EUR0603"))
    )
    (comp (ref "R18")
      (value "4k7")
      (footprint "eagle-import:R0603")
      (libsource (lib "eagle-import") (part "R-EUR0603"))
    )
    (comp (ref "R19")
      (value "4k7")
      (footprint "eagle-import:R0603")
      (libsource (lib "eagle-import") (part "R-EUR0603"))
    )
    (comp (ref "R20")
      (value "100R")
      (footprint "eagle-import:R0603")
      (libsource (lib "eagle-import") (part "R-EUR0603"))
    )
    (comp (ref "R21")
      (value "100R")
      (footprint "eagle-import:R0603")
      (libsource (lib "eagle-import") (part "R-EUR0603"))
    )
    (comp (ref "R22")
      (value "100R")
      (footprint "eagle-import:R0603")
      (libsource (lib "eagle-import") (part "R-EUR0603"))
    )
    (comp (ref "R23")
      (value "100R")
      (footprint "eagle-import:R0603")
      (libsource (lib "eagle-import") (part "R-EUR0603"))
    )
    (comp (ref "R24")
      (value "100R")
      (footprint "eagle-import:R0603")
      (libsource (lib "eagle-import") (part "R-EUR0603"))
    )
    (comp (ref "R25")
      (value "DNF")
      (footprint "eagle-import:R0603")
      (libsource (lib "eagle-import") (part "R-EUR0603"))
    )
    (comp (ref "R26")
      (value "100R")
      (footprint "eagle-import:R0603")
      (libsource (lib "eagle-import") (part "R-EUR0603"))
    )
    (comp (ref "R27")
      (value "DNF")
      (footprint "eagle-import:R0603")
      (libsource (lib "eagle-import") (part "R-EUR0603"))
    )
    (comp (ref "R28")
      (value "4k7")
      (footprint "eagle-import:R0603")
      (libsource (lib "eagle-import") (part "R-EUR0603"))
    )
    (comp (ref "R29")
      (value "4k7")
      (footprint "eagle-import:R0603")
      (libsource (lib "eagle-import") (part "R-EUR0603"))
    )
    (comp (ref "R30")
      (value "4k7")
      (footprint "eagle-import:R0603")
      (libsource (lib "eagle-import") (part "R-EUR0603"))
    )
    (comp (ref "R31")
      (value "4k7")
      (footprint "eagle-import:R0603")
      (libsource (lib "eagle-import") (part "R-EUR0603"))
    )
    (comp (ref "U1")
      (value "ADC121S101-Q")
      (footprint "eagle-import:SOT23-6")
      (libsource (lib "eagle-import") (part "ADC121S101-Q"))
    )
    (comp (ref "U2")
      (value "SI8641AB-B-IS1R")
      (footprint "eagle-import:SO16")
      (libsource (lib "eagle-import") (part "SI8641SO16"))
    )
    (comp (ref "U3")
      (value "SI8641AB-B-IS1R")
      (footprint "eagle-import:SO16")
      (libsource (lib "eagle-import") (part "SI8641SO16"))
    )
  )
  (nets
    (net (code "1") (name "+4V") (class "Default")
      (node (ref "C44") (pin "1") (pinfunction "1_1") (pintype "passive"))
      (node (ref "C45") (pin "1") (pinfunction "1_1") (pintype "passive"))
      (node (ref "C46") (pin "1") (pinfunction "1_1") (pintype "passive"))
      (node (ref "C47") (pin "1") (pinfunction "1_1") (pintype "passive"))
      (node (ref "C48") (pin "1") (pinfunction "1_1") (pintype "passive"))
      (node (ref "L2") (pin "2") (pinfunction "2_2") (pintype "passive"))
      (node (ref "X10") (pin "2") (pinfunction "2_2") (pintype "passive"))
    )
    (net (code "2") (name "+5V") (class "Default")
      (node (ref "C1") (pin "1") (pinfunction "1_1") (pintype "passive"))
      (node (ref "C10") (pin "1") (pinfunction "1_1") (pintype "passive"))
      (node (ref "C13") (pin "1") (pinfunction "1_1") (pintype "passive"))
      (node (ref "C15") (pin "1") (pinfunction "1_1") (pintype "passive"))
      (node (ref "C17") (pin "1") (pinfunction "1_1") (pintype "passive"))
      (node (ref "C19") (pin "1") (pinfunction "1_1") (pintype "passive"))
      (node (ref "C4") (pin "1") (pinfunction "1_1") (pintype "passive"))
      (node (ref "C49") (pin "1") (pinfunction "1_1") (pintype "passive"))
      (node (ref "C50") (pin "1") (pinfunction "1_1") (pintype "passive"))
      (node (ref "C51") (pin "1") (pinfunction "1_1") (pintype "passive"))
      (node (ref "C52") (pin "1") (pinfunction "1_1") (pintype "passive"))
      (node (ref "C65") (pin "1") (pinfunction "1_1") (pintype "passive"))
      (node (ref "C67") (pin "1") (pinfunction "1_1") (pintype "passive"))
      (node (ref "C68") (pin "1") (pinfunction "1_1") (pintype "passive"))
      (node (ref "C69") (pin "1") (pinfunction "1_1") (pintype "passive"))
      (node (ref "C7") (pin "1") (pinfunction "1_1") (pintype "passive"))
      (node (ref "C70") (pin "1") (pinfunction "1_1") (pintype "passive"))
      (node (ref "C71") (pin "1") (pinfunction "1_1") (pintype "passive"))
      (node (ref "C72") (pin "1") (pinfunction "1_1") (pintype "passive"))
      (node (ref "C73") (pin "1") (pinfunction "1_1") (pintype "passive"))
      (node (ref "C75") (pin "1") (pinfunction "1_1") (pintype "passive"))
      (node (ref "C76") (pin "1") (pinfunction "1_1") (pintype "passive"))
      (node (ref "C77") (pin "1") (pinfunction "1_1") (pintype "passive"))
      (node (ref "C78") (pin "1") (pinfunction "1_1") (pintype "passive"))
      (node (ref "C83") (pin "1") (pinfunction "1_1") (pintype "passive"))
      (node (ref "C84") (pin "1") (pinfunction "1_1") (pintype "passive"))
      (node (ref "C85") (pin "1") (pinfunction "1_1") (pintype "passive"))
      (node (ref "C86") (pin "1") (pinfunction "1_1") (pintype "passive"))
      (node (ref "C88") (pin "1") (pinfunction "1_1") (pintype "passive"))
      (node (ref "C89") (pin "1") (pinfunction "1_1") (pintype "passive"))
      (node (ref "C90") (pin "1") (pinfunction "1_1") (pintype "passive"))
      (node (ref "C91") (pin "1") (pinfunction "1_1") (pintype "passive"))
      (node (ref "C92") (pin "1") (pinfunction "1_1") (pintype "passive"))
      (node (ref "C93") (pin "1") (pinfunction "1_1") (pintype "passive"))
      (node (ref "C94") (pin "1") (pinfunction "1_1") (pintype "passive"))
      (node (ref "C95") (pin "1") (pinfunction "1_1") (pintype "passive"))
      (node (ref "IC1") (pin "5") (pinfunction "V+_5") (pintype "power_in"))
      (node (ref "IC2") (pin "5") (pinfunction "V+_5") (pintype "power_in"))
      (node (ref "P3") (pin "10") (pinfunction "10_10") (pintype "passive"))
      (node (ref "P3") (pin "2") (pinfunction "2_2") (pintype "passive"))
      (node (ref "P3") (pin "4") (pinfunction "4_4") (pintype "passive"))
      (node (ref "P3") (pin "6") (pinfunction "6_6") (pintype "passive"))
      (node (ref "P3") (pin "8") (pinfunction "8_8") (pintype "passive"))
      (node (ref "R19") (pin "2") (pinfunction "2_2") (pintype "passive"))
      (node (ref "R43") (pin "2") (pinfunction "2_2") (pintype "passive"))
      (node (ref "R52") (pin "2") (pinfunction "2_2") (pintype "passive"))
      (node (ref "R7") (pin "2") (pinfunction "2_2") (pintype "passive"))
      (node (ref "U2") (pin "1") (pinfunction "VDD1_1") (pintype "power_in"))
      (node (ref "U3") (pin "1") (pinfunction "VDD1_1") (pintype "power_in"))
      (node (ref "U4") (pin "1") (pinfunction "VA_1") (pintype "power_in"))
      (node (ref "U5") (pin "10") (pinfunction "VCC_10") (pintype "bidirectional"))
      (node (ref "U6") (pin "1") (pinfunction "VA_1") (pintype "power_in"))
      (node (ref "U7") (pin "10") (pinfunction "VCC_10") (pintype "bidirectional"))
      (node (ref "VR3") (pin "+V") (pinfunction "V+_+V") (pintype "passive"))
      (node (ref "X11") (pin "2") (pinfunction "2_2") (pintype "passive"))
    )
    (net (code "3") (name "+12V") (class "Default")
      (node (ref "C40") (pin "1") (pinfunction "1_1") (pintype "passive"))
      (node (ref "C41") (pin "1") (pinfunction "1_1") (pintype "passive"))
      (node (ref "C42") (pin "1") (pinfunction "1_1") (pintype "passive"))
      (node (ref "C43") (pin "1") (pinfunction "1_1") (pintype "passive"))
      (node (ref "C53") (pin "1") (pinfunction "1_1") (pintype "passive"))
      (node (ref "C54") (pin "1") (pinfunction "1_1") (pintype "passive"))
      (node (ref "C55") (pin "1") (pinfunction "1_1") (pintype "passive"))
      (node (ref "C56") (pin "1") (pinfunction "1_1") (pintype "passive"))
      (node (ref "P3") (pin "1") (pinfunction "1_1") (pintype "passive"))
      (node (ref "P3") (pin "3") (pinfunction "3_3") (pintype "passive"))
      (node (ref "P3") (pin "5") (pinfunction "5_5") (pintype "passive"))
      (node (ref "P3") (pin "7") (pinfunction "7_7") (pintype "passive"))
      (node (ref "P3") (pin "9") (pinfunction "9_9") (pintype "passive"))
      (node (ref "R33") (pin "2") (pinfunction "2_2") (pintype "passive"))
      (node (ref "VR2") (pin "3") (pinfunction "VIN_3") (pintype "bidirectional"))
      (node (ref "VR4") (pin "+V") (pinfunction "V+_+V") (pintype "passive"))
      (node (ref "X12") (pin "2") (pinfunction "2_2") (pintype "passive"))
      (node (ref "X13") (pin "2") (pinfunction "2_2") (pintype "passive"))
    )
    (net (code "4") (name "AC{slash}L") (class "Default")
      (node (ref "C22") (pin "1") (pinfunction "1_1") (pintype "passive"))
      (node (ref "C24") (pin "1") (pinfunction "1_1") (pintype "passive"))
      (node (ref "L1") (pin "3") (pinfunction "2_3") (pintype "passive"))
      (node (ref "VR1") (pin "AC/L") (pinfunction "AC/L_AC/L") (pintype "passive"))
      (node (ref "VR3") (pin "AC/L") (pinfunction "AC/L_AC/L") (pintype "passive"))
      (node (ref "VR4") (pin "AC/L") (pinfunction "AC/L_AC/L") (pintype "passive"))
      (node (ref "X3") (pin "3") (pinfunction "3_3") (pintype "passive"))
      (node (ref "X5") (pin "3") (pinfunction "3_3") (pintype "passive"))
      (node (ref "X6") (pin "3") (pinfunction "3_3") (pintype "passive"))
    )
    (net (code "5") (name "AC{slash}N") (class "Default")
      (node (ref "C24") (pin "2") (pinfunction "2_2") (pintype "passive"))
      (node (ref "C26") (pin "2") (pinfunction "2_2") (pintype "passive"))
      (node (ref "L1") (pin "2") (pinfunction "3_2") (pintype "passive"))
      (node (ref "VR1") (pin "AC/N") (pinfunction "AC/N_AC/N") (pintype "passive"))
      (node (ref "VR3") (pin "AC/N") (pinfunction "AC/N_AC/N") (pintype "passive"))
      (node (ref "VR4") (pin "AC/N") (pinfunction "AC/N_AC/N") (pintype "passive"))
      (node (ref "X3") (pin "1") (pinfunction "1_1") (pintype "passive"))
      (node (ref "X5") (pin "1") (pinfunction "1_1") (pintype "passive"))
      (node (ref "X6") (pin "1") (pinfunction "1_1") (pintype "passive"))
    )
    (net (code "6") (name "EARTH") (class "Default")
      (node (ref "C21") (pin "2") (pinfunction "2_2") (pintype "passive"))
      (node (ref "C22") (pin "2") (pinfunction "2_2") (pintype "passive"))
      (node (ref "C25") (pin "1") (pinfunction "1_1") (pintype "passive"))
      (node (ref "C26") (pin "1") (pinfunction "1_1") (pintype "passive"))
      (node (ref "X1") (pin "2") (pinfunction "2_2") (pintype "passive"))
      (node (ref "X3") (pin "2") (pinfunction "2_2") (pintype "passive"))
      (node (ref "X5") (pin "2") (pinfunction "2_2") (pintype "passive"))
      (node (ref "X6") (pin "2") (pinfunction "2_2") (pintype "passive"))
    )
    (net (code "7") (name "GND") (class "Default")
      (node (ref "C1") (pin "2") (pinfunction "2_2") (pintype "passive"))
      (node (ref "C10") (pin "2") (pinfunction "2_2") (pintype "passive"))
      (node (ref "C13") (pin "2") (pinfunction "2_2") (pintype "passive"))
      (node (ref "C15") (pin "2") (pinfunction "2_2") (pintype "passive"))
      (node (ref "C17") (pin "2") (pinfunction "2_2") (pintype "passive"))
      (node (ref "C19") (pin "2") (pinfunction "2_2") (pintype "passive"))
      (node (ref "C4") (pin "2") (pinfunction "2_2") (pintype "passive"))
      (node (ref "C40") (pin "2") (pinfunction "2_2") (pintype "passive"))
      (node (ref "C41") (pin "2") (pinfunction "2_2") (pintype "passive"))
      (node (ref "C42") (pin "2") (pinfunction "2_2") (pintype "passive"))
      (node (ref "C43") (pin "2") (pinfunction "2_2") (pintype "passive"))
      (node (ref "C44") (pin "2") (pinfunction "2_2") (pintype "passive"))
      (node (ref "C45") (pin "2") (pinfunction "2_2") (pintype "passive"))
      (node (ref "C46") (pin "2") (pinfunction "2_2") (pintype "passive"))
      (node (ref "C47") (pin "2") (pinfunction "2_2") (pintype "passive"))
      (node (ref "C48") (pin "2") (pinfunction "2_2") (pintype "passive"))
      (node (ref "C49") (pin "2") (pinfunction "2_2") (pintype "passive"))
      (node (ref "C50") (pin "2") (pinfunction "2_2") (pintype "passive"))
      (node (ref "C51") (pin "2") (pinfunction "2_2") (pintype "passive"))
      (node (ref "C52") (pin "2") (pinfunction "2_2") (pintype "passive"))
      (node (ref "C53") (pin "2") (pinfunction "2_2") (pintype "passive"))
      (node (ref "C54") (pin "2") (pinfunction "2_2") (pintype "passive"))
      (node (ref "C55") (pin "2") (pinfunction "2_2") (pintype "passive"))
      (node (ref "C56") (pin "2") (pinfunction "2_2") (pintype "passive"))
      (node (ref "C65") (pin "2") (pinfunction "2_2") (pintype "passive"))
      (node (ref "C67") (pin "2") (pinfunction "2_2") (pintype "passive"))
      (node (ref "C68") (pin "2") (pinfunction "2_2") (pintype "passive"))
      (node (ref "C69") (pin "2") (pinfunction "2_2") (pintype "passive"))
      (node (ref "C7") (pin "2") (pinfunction "2_2") (pintype "passive"))
      (node (ref "C70") (pin "2") (pinfunction "2_2") (pintype "passive"))
      (node (ref "C71") (pin "2") (pinfunction "2_2") (pintype "passive"))
      (node (ref "C72") (pin "2") (pinfunction "2_2") (pintype "passive"))
      (node (ref "C73") (pin "2") (pinfunction "2_2") (pintype "passive"))
      (node (ref "C75") (pin "2") (pinfunction "2_2") (pintype "passive"))
      (node (ref "C76") (pin "2") (pinfunction "2_2") (pintype "passive"))
      (node (ref "C77") (pin "2") (pinfunction "2_2") (pintype "passive"))
      (node (ref "C78") (pin "2") (pinfunction "2_2") (pintype "passive"))
      (node (ref "C80") (pin "2") (pinfunction "2_2") (pintype "passive"))
      (node (ref "C83") (pin "2") (pinfunction "2_2") (pintype "passive"))
      (node (ref "C84") (pin "2") (pinfunction "2_2") (pintype "passive"))
      (node (ref "C85") (pin "2") (pinfunction "2_2") (pintype "passive"))
      (node (ref "C86") (pin "2") (pinfunction "2_2") (pintype "passive"))
      (node (ref "C88") (pin "2") (pinfunction "2_2") (pintype "passive"))
      (node (ref "C89") (pin "2") (pinfunction "2_2") (pintype "passive"))
      (node (ref "C90") (pin "2") (pinfunction "2_2") (pintype "passive"))
      (node (ref "C91") (pin "2") (pinfunction "2_2") (pintype "passive"))
      (node (ref "C92") (pin "2") (pinfunction "2_2") (pintype "passive"))
      (node (ref "C93") (pin "2") (pinfunction "2_2") (pintype "passive"))
      (node (ref "C94") (pin "2") (pinfunction "2_2") (pintype "passive"))
      (node (ref "C95") (pin "2") (pinfunction "2_2") (pintype "passive"))
      (node (ref "C96") (pin "2") (pinfunction "2_2") (pintype "passive"))
      (node (ref "IC1") (pin "2") (pinfunction "V-_2") (pintype "power_in"))
      (node (ref "IC2") (pin "2") (pinfunction "V-_2") (pintype "power_in"))
      (node (ref "P1") (pin "10") (pinfunction "10_10") (pintype "passive"))
      (node (ref "P1") (pin "11") (pinfunction "11_11") (pintype "passive"))
      (node (ref "P1") (pin "12") (pinfunction "12_12") (pintype "passive"))
      (node (ref "P1") (pin "13") (pinfunction "13_13") (pintype "passive"))
      (node (ref "P1") (pin "14") (pinfunction "14_14") (pintype "passive"))
      (node (ref "P1") (pin "15") (pinfunction "15_15") (pintype "passive"))
      (node (ref "P1") (pin "16") (pinfunction "16_16") (pintype "passive"))
      (node (ref "P1") (pin "17") (pinfunction "17_17") (pintype "passive"))
      (node (ref "P1") (pin "18") (pinfunction "18_18") (pintype "passive"))
      (node (ref "P1") (pin "19") (pinfunction "19_19") (pintype "passive"))
      (node (ref "P1") (pin "20") (pinfunction "20_20") (pintype "passive"))
      (node (ref "P1") (pin "9") (pinfunction "9_9") (pintype "passive"))
      (node (ref "P3") (pin "11") (pinfunction "11_11") (pintype "passive"))
      (node (ref "P3") (pin "12") (pinfunction "12_12") (pintype "passive"))
      (node (ref "P3") (pin "13") (pinfunction "13_13") (pintype "passive"))
      (node (ref "P3") (pin "14") (pinfunction "14_14") (pintype "passive"))
      (node (ref "P3") (pin "15") (pinfunction "15_15") (pintype "passive"))
      (node (ref "P3") (pin "16") (pinfunction "16_16") (pintype "passive"))
      (node (ref "P3") (pin "17") (pinfunction "17_17") (pintype "passive"))
      (node (ref "P3") (pin "18") (pinfunction "18_18") (pintype "passive"))
      (node (ref "P3") (pin "19") (pinfunction "19_19") (pintype "passive"))
      (node (ref "P3") (pin "20") (pinfunction "20_20") (pintype "passive"))
      (node (ref "R28") (pin "1") (pinfunction "1_1") (pintype "passive"))
      (node (ref "R29") (pin "1") (pinfunction "1_1") (pintype "passive"))
      (node (ref "R35") (pin "1") (pinfunction "1_1") (pintype "passive"))
      (node (ref "R36") (pin "1") (pinfunction "1_1") (pintype "passive"))
      (node (ref "R47") (pin "1") (pinfunction "1_1") (pintype "passive"))
      (node (ref "R48") (pin "1") (pinfunction "1_1") (pintype "passive"))
      (node (ref "R55") (pin "1") (pinfunction "1_1") (pintype "passive"))
      (node (ref "R56") (pin "1") (pinfunction "1_1") (pintype "passive"))
      (node (ref "U2") (pin "2") (pinfunction "GND1_2") (pintype "power_in"))
      (node (ref "U2") (pin "8") (pinfunction "GND1_8") (pintype "power_in"))
      (node (ref "U3") (pin "2") (pinfunction "GND1_2") (pintype "power_in"))
      (node (ref "U3") (pin "8") (pinfunction "GND1_8") (pintype "power_in"))
      (node (ref "U4") (pin "2") (pinfunction "GND_2") (pintype "power_in"))
      (node (ref "U5") (pin "11") (pinfunction "GND_11") (pintype "bidirectional"))
      (node (ref "U5") (pin "14") (pinfunction "GND_14") (pintype "bidirectional"))
      (node (ref "U5") (pin "15") (pinfunction "GND_15") (pintype "bidirectional"))
      (node (ref "U6") (pin "2") (pinfunction "GND_2") (pintype "power_in"))
      (node (ref "U7") (pin "11") (pinfunction "GND_11") (pintype "bidirectional"))
      (node (ref "U7") (pin "14") (pinfunction "GND_14") (pintype "bidirectional"))
      (node (ref "U7") (pin "15") (pinfunction "GND_15") (pintype "bidirectional"))
      (node (ref "VR2") (pin "1") (pinfunction "GND_1") (pintype "bidirectional"))
      (node (ref "VR3") (pin "-V") (pinfunction "V-_-V") (pintype "passive"))
      (node (ref "VR4") (pin "-V") (pinfunction "V-_-V") (pintype "passive"))
      (node (ref "X10") (pin "1") (pinfunction "1_1") (pintype "passive"))
      (node (ref "X11") (pin "1") (pinfunction "1_1") (pintype "passive"))
      (node (ref "X12") (pin "1") (pinfunction "1_1") (pintype "passive"))
      (node (ref "X13") (pin "1") (pinfunction "1_1") (pintype "passive"))
    )
    (net (code "8") (name "GRID_CURR_AMP") (class "Default")
      (node (ref "R44") (pin "1") (pinfunction "1_1") (pintype "passive"))
      (node (ref "R57") (pin "1") (pinfunction "1_1") (pintype "passive"))
      (node (ref "U4") (pin "3") (pinfunction "VIN_3") (pintype "input"))
    )
    (net (code "9") (name "GRID_CURR_FAULT") (class "Default")
      (node (ref "TP2") (pin "TP") (pinfunction "TP_TP") (pintype "input"))
      (node (ref "U5") (pin "9") (pinfunction "~{FAULTB}_9") (pintype "bidirectional"))
    )
    (net (code "10") (name "GRID_CURR_OUT") (class "Default")
      (node (ref "IC1") (pin "1") (pinfunction "+IN_1") (pintype "input"))
      (node (ref "R44") (pin "2") (pinfunction "2_2") (pintype "passive"))
      (node (ref "U5") (pin "12") (pinfunction "VOUT_12") (pintype "bidirectional"))
    )
    (net (code "11") (name "Net-(C39-Pad1)") (class "Default")
      (node (ref "C39") (pin "1") (pinfunction "1_1") (pintype "passive"))
      (node (ref "R32") (pin "2") (pinfunction "2_2") (pintype "passive"))
    )
    (net (code "12") (name "Net-(C57-Pad2)") (class "Default")
      (node (ref "C57") (pin "2") (pinfunction "2_2") (pintype "passive"))
      (node (ref "C58") (pin "2") (pinfunction "2_2") (pintype "passive"))
      (node (ref "C59") (pin "2") (pinfunction "2_2") (pintype "passive"))
      (node (ref "C61") (pin "1") (pinfunction "1_1") (pintype "passive"))
      (node (ref "C62") (pin "1") (pinfunction "1_1") (pintype "passive"))
      (node (ref "C63") (pin "1") (pinfunction "1_1") (pintype "passive"))
      (node (ref "R37") (pin "1") (pinfunction "1_1") (pintype "passive"))
      (node (ref "R39") (pin "2") (pinfunction "2_2") (pintype "passive"))
    )
    (net (code "13") (name "Net-(C60--)") (class "Default")
      (node (ref "C60") (pin "-VE") (pinfunction "-_-VE") (pintype "passive"))
      (node (ref "C64") (pin "+VE") (pinfunction "+_+VE") (pintype "passive"))
      (node (ref "R38") (pin "1") (pinfunction "1_1") (pintype "passive"))
      (node (ref "R40") (pin "2") (pinfunction "2_2") (pintype "passive"))
    )
    (net (code "14") (name "Net-(C64--)") (class "Default")
      (node (ref "C64") (pin "-VE") (pinfunction "-_-VE") (pintype "passive"))
      (node (ref "C66") (pin "+VE") (pinfunction "+_+VE") (pintype "passive"))
      (node (ref "R40") (pin "1") (pinfunction "1_1") (pintype "passive"))
      (node (ref "R41") (pin "2") (pinfunction "2_2") (pintype "passive"))
    )
    (net (code "15") (name "Net-(C66--)") (class "Default")
      (node (ref "C66") (pin "-VE") (pinfunction "-_-VE") (pintype "passive"))
      (node (ref "C74") (pin "+VE") (pinfunction "+_+VE") (pintype "passive"))
      (node (ref "R41") (pin "1") (pinfunction "1_1") (pintype "passive"))
      (node (ref "R42") (pin "2") (pinfunction "2_2") (pintype "passive"))
    )
    (net (code "16") (name "Net-(C74--)") (class "Default")
      (node (ref "C74") (pin "-VE") (pinfunction "-_-VE") (pintype "passive"))
      (node (ref "C79") (pin "+VE") (pinfunction "+_+VE") (pintype "passive"))
      (node (ref "R42") (pin "1") (pinfunction "1_1") (pintype "passive"))
      (node (ref "R45") (pin "2") (pinfunction "2_2") (pintype "passive"))
    )
    (net (code "17") (name "Net-(C79--)") (class "Default")
      (node (ref "C79") (pin "-VE") (pinfunction "-_-VE") (pintype "passive"))
      (node (ref "C81") (pin "+VE") (pinfunction "+_+VE") (pintype "passive"))
      (node (ref "R45") (pin "1") (pinfunction "1_1") (pintype "passive"))
      (node (ref "R49") (pin "2") (pinfunction "2_2") (pintype "passive"))
    )
    (net (code "18") (name "Net-(C81--)") (class "Default")
      (node (ref "C81") (pin "-VE") (pinfunction "-_-VE") (pintype "passive"))
      (node (ref "C82") (pin "+VE") (pinfunction "+_+VE") (pintype "passive"))
      (node (ref "R49") (pin "1") (pinfunction "1_1") (pintype "passive"))
      (node (ref "R50") (pin "2") (pinfunction "2_2") (pintype "passive"))
    )
    (net (code "19") (name "Net-(D1-ANODE)") (class "Default")
      (node (ref "D1") (pin "A") (pinfunction "ANODE_A") (pintype "bidirectional"))
      (node (ref "D2") (pin "C") (pinfunction "CATHODE_C") (pintype "bidirectional"))
      (node (ref "R15") (pin "2") (pinfunction "2_2") (pintype "passive"))
      (node (ref "R8") (pin "1") (pinfunction "1_1") (pintype "passive"))
      (node (ref "U1") (pin "3") (pinfunction "VIN_3") (pintype "input"))
    )
    (net (code "20") (name "Net-(D3-PadA)") (class "Default")
      (node (ref "D3") (pin "A") (pinfunction "A_A") (pintype "passive"))
      (node (ref "D5") (pin "C") (pinfunction "C_C") (pintype "passive"))
      (node (ref "X4") (pin "2") (pinfunction "2_2") (pintype "passive"))
    )
    (net (code "21") (name "Net-(D4-PadA)") (class "Default")
      (node (ref "D4") (pin "A") (pinfunction "A_A") (pintype "passive"))
      (node (ref "D6") (pin "C") (pinfunction "C_C") (pintype "passive"))
      (node (ref "X4") (pin "1") (pinfunction "1_1") (pintype "passive"))
    )
    (net (code "22") (name "Net-(D7-PadA)") (class "Default")
      (node (ref "D7") (pin "A") (pinfunction "A_A") (pintype "passive"))
      (node (ref "D9") (pin "C") (pinfunction "C_C") (pintype "passive"))
      (node (ref "X8") (pin "2") (pinfunction "2_2") (pintype "passive"))
    )
    (net (code "23") (name "Net-(D10-PadC)") (class "Default")
      (node (ref "D10") (pin "C") (pinfunction "C_C") (pintype "passive"))
      (node (ref "D8") (pin "A") (pinfunction "A_A") (pintype "passive"))
      (node (ref "X8") (pin "1") (pinfunction "1_1") (pintype "passive"))
    )
    (net (code "24") (name "Net-(D11-ANODE)") (class "Default")
      (node (ref "D11") (pin "1") (pinfunction "ANODE_1") (pintype "bidirectional"))
      (node (ref "D13") (pin "3") (pinfunction "CATHODE_3") (pintype "bidirectional"))
    )
    (net (code "25") (name "Net-(D12-ANODE)") (class "Default")
      (node (ref "D12") (pin "1") (pinfunction "ANODE_1") (pintype "bidirectional"))
      (node (ref "D14") (pin "3") (pinfunction "CATHODE_3") (pintype "bidirectional"))
    )
    (net (code "26") (name "Net-(D13-ANODE)") (class "Default")
      (node (ref "D13") (pin "1") (pinfunction "ANODE_1") (pintype "bidirectional"))
      (node (ref "D15") (pin "3") (pinfunction "CATHODE_3") (pintype "bidirectional"))
      (node (ref "X15") (pin "1") (pinfunction "1_1") (pintype "passive"))
      (node (ref "X15") (pin "2") (pinfunction "2_2") (pintype "passive"))
    )
    (net (code "27") (name "Net-(D14-ANODE)") (class "Default")
      (node (ref "D14") (pin "1") (pinfunction "ANODE_1") (pintype "bidirectional"))
      (node (ref "D16") (pin "3") (pinfunction "CATHODE_3") (pintype "bidirectional"))
      (node (ref "X16") (pin "1") (pinfunction "1_1") (pintype "passive"))
      (node (ref "X16") (pin "2") (pinfunction "2_2") (pintype "passive"))
    )
    (net (code "28") (name "Net-(D15-ANODE)") (class "Default")
      (node (ref "D15") (pin "1") (pinfunction "ANODE_1") (pintype "bidirectional"))
      (node (ref "D18") (pin "3") (pinfunction "CATHODE_3") (pintype "bidirectional"))
    )
    (net (code "29") (name "Net-(D16-ANODE)") (class "Default")
      (node (ref "D16") (pin "1") (pinfunction "ANODE_1") (pintype "bidirectional"))
      (node (ref "D17") (pin "3") (pinfunction "CATHODE_3") (pintype "bidirectional"))
    )
    (net (code "30") (name "Net-(IC1--IN)") (class "Default")
      (node (ref "IC1") (pin "3") (pinfunction "-IN_3") (pintype "input"))
      (node (ref "R46") (pin "2") (pinfunction "2_2") (pintype "passive"))
      (node (ref "R48") (pin "2") (pinfunction "2_2") (pintype "passive"))
    )
    (net (code "31") (name "Net-(IC1-OUT)") (class "Default")
      (node (ref "IC1") (pin "4") (pinfunction "OUT_4") (pintype "output"))
      (node (ref "R46") (pin "1") (pinfunction "1_1") (pintype "passive"))
      (node (ref "R57") (pin "2") (pinfunction "2_2") (pintype "passive"))
    )
    (net (code "32") (name "Net-(IC2--IN)") (class "Default")
      (node (ref "IC2") (pin "3") (pinfunction "-IN_3") (pintype "input"))
      (node (ref "R54") (pin "2") (pinfunction "2_2") (pintype "passive"))
      (node (ref "R55") (pin "2") (pinfunction "2_2") (pintype "passive"))
    )
    (net (code "33") (name "Net-(IC2-OUT)") (class "Default")
      (node (ref "IC2") (pin "4") (pinfunction "OUT_4") (pintype "output"))
      (node (ref "R51") (pin "2") (pinfunction "2_2") (pintype "passive"))
      (node (ref "R54") (pin "1") (pinfunction "1_1") (pintype "passive"))
    )
    (net (code "34") (name "Net-(L1-1)") (class "Default")
      (node (ref "C21") (pin "1") (pinfunction "1_1") (pintype "passive"))
      (node (ref "C23") (pin "1") (pinfunction "1_1") (pintype "passive"))
      (node (ref "L1") (pin "4") (pinfunction "1_4") (pintype "passive"))
      (node (ref "X1") (pin "1") (pinfunction "1_1") (pintype "passive"))
    )
    (net (code "35") (name "Net-(L1-4)") (class "Default")
      (node (ref "C23") (pin "2") (pinfunction "2_2") (pintype "passive"))
      (node (ref "C25") (pin "2") (pinfunction "2_2") (pintype "passive"))
      (node (ref "L1") (pin "1") (pinfunction "4_1") (pintype "passive"))
      (node (ref "X1") (pin "3") (pinfunction "3_3") (pintype "passive"))
    )
    (net (code "36") (name "Net-(R1-Pad2)") (class "Default")
      (node (ref "R1") (pin "2") (pinfunction "2_2") (pintype "passive"))
      (node (ref "R2") (pin "2") (pinfunction "2_2") (pintype "passive"))
    )
    (net (code "37") (name "Net-(R2-Pad1)") (class "Default")
      (node (ref "R2") (pin "1") (pinfunction "1_1") (pintype "passive"))
      (node (ref "R3") (pin "1") (pinfunction "1_1") (pintype "passive"))
    )
    (net (code "38") (name "Net-(R3-Pad2)") (class "Default")
      (node (ref "R3") (pin "2") (pinfunction "2_2") (pintype "passive"))
      (node (ref "R4") (pin "2") (pinfunction "2_2") (pintype "passive"))
    )
    (net (code "39") (name "Net-(R4-Pad1)") (class "Default")
      (node (ref "R4") (pin "1") (pinfunction "1_1") (pintype "passive"))
      (node (ref "R6") (pin "1") (pinfunction "1_1") (pintype "passive"))
    )
    (net (code "40") (name "Net-(R6-Pad2)") (class "Default")
      (node (ref "R6") (pin "2") (pinfunction "2_2") (pintype "passive"))
      (node (ref "R8") (pin "2") (pinfunction "2_2") (pintype "passive"))
    )
    (net (code "41") (name "Net-(R24-Pad1)") (class "Default")
      (node (ref "R24") (pin "1") (pinfunction "1_1") (pintype "passive"))
      (node (ref "R28") (pin "2") (pinfunction "2_2") (pintype "passive"))
    )
    (net (code "42") (name "Net-(R26-Pad1)") (class "Default")
      (node (ref "R26") (pin "1") (pinfunction "1_1") (pintype "passive"))
      (node (ref "R29") (pin "2") (pinfunction "2_2") (pintype "passive"))
    )
    (net (code "43") (name "Net-(U1-~{CS})") (class "Default")
      (node (ref "R10") (pin "2") (pinfunction "2_2") (pintype "passive"))
      (node (ref "U1") (pin "6") (pinfunction "~{CS}_6") (pintype "passive"))
    )
    (net (code "44") (name "Net-(U2-A1)") (class "Default")
      (node (ref "R9") (pin "2") (pinfunction "2_2") (pintype "passive"))
      (node (ref "U2") (pin "3") (pinfunction "A1_3") (pintype "bidirectional"))
    )
    (net (code "45") (name "Net-(U2-A2)") (class "Default")
      (node (ref "R11") (pin "2") (pinfunction "2_2") (pintype "passive"))
      (node (ref "U2") (pin "4") (pinfunction "A2_4") (pintype "bidirectional"))
    )
    (net (code "46") (name "Net-(U2-A3)") (class "Default")
      (node (ref "R13") (pin "2") (pinfunction "2_2") (pintype "passive"))
      (node (ref "U2") (pin "5") (pinfunction "A3_5") (pintype "bidirectional"))
    )
    (net (code "47") (name "Net-(U2-A4)") (class "Default")
      (node (ref "R16") (pin "2") (pinfunction "2_2") (pintype "passive"))
      (node (ref "U2") (pin "6") (pinfunction "A4_6") (pintype "bidirectional"))
    )
    (net (code "48") (name "Net-(U2-B1)") (class "Default")
      (node (ref "R10") (pin "1") (pinfunction "1_1") (pintype "passive"))
      (node (ref "U2") (pin "14") (pinfunction "B1_14") (pintype "bidirectional"))
    )
    (net (code "49") (name "Net-(U2-B2)") (class "Default")
      (node (ref "R12") (pin "1") (pinfunction "1_1") (pintype "passive"))
      (node (ref "U2") (pin "13") (pinfunction "B2_13") (pintype "bidirectional"))
    )
    (net (code "50") (name "Net-(U2-B3)") (class "Default")
      (node (ref "R14") (pin "1") (pinfunction "1_1") (pintype "passive"))
      (node (ref "U2") (pin "12") (pinfunction "B3_12") (pintype "bidirectional"))
    )
    (net (code "51") (name "Net-(U2-B4)") (class "Default")
      (node (ref "R17") (pin "1") (pinfunction "1_1") (pintype "passive"))
      (node (ref "U2") (pin "11") (pinfunction "B4_11") (pintype "bidirectional"))
    )
    (net (code "52") (name "Net-(U2-EN1)") (class "Default")
      (node (ref "R7") (pin "1") (pinfunction "1_1") (pintype "passive"))
      (node (ref "U2") (pin "7") (pinfunction "EN1_7") (pintype "bidirectional"))
    )
    (net (code "53") (name "Net-(U2-EN2)") (class "Default")
      (node (ref "R5") (pin "1") (pinfunction "1_1") (pintype "passive"))
      (node (ref "U2") (pin "10") (pinfunction "EN2_10") (pintype "bidirectional"))
    )
    (net (code "54") (name "Net-(U3-A1)") (class "Default")
      (node (ref "R20") (pin "2") (pinfunction "2_2") (pintype "passive"))
      (node (ref "U3") (pin "3") (pinfunction "A1_3") (pintype "bidirectional"))
    )
    (net (code "55") (name "Net-(U3-A2)") (class "Default")
      (node (ref "R22") (pin "2") (pinfunction "2_2") (pintype "passive"))
      (node (ref "U3") (pin "4") (pinfunction "A2_4") (pintype "bidirectional"))
    )
    (net (code "56") (name "Net-(U3-A3)") (class "Default")
      (node (ref "R24") (pin "2") (pinfunction "2_2") (pintype "passive"))
      (node (ref "U3") (pin "5") (pinfunction "A3_5") (pintype "bidirectional"))
    )
    (net (code "57") (name "Net-(U3-A4)") (class "Default")
      (node (ref "R26") (pin "2") (pinfunction "2_2") (pintype "passive"))
      (node (ref "U3") (pin "6") (pinfunction "A4_6") (pintype "bidirectional"))
    )
    (net (code "58") (name "Net-(U3-B1)") (class "Default")
      (node (ref "R21") (pin "1") (pinfunction "1_1") (pintype "passive"))
      (node (ref "U3") (pin "14") (pinfunction "B1_14") (pintype "bidirectional"))
    )
    (net (code "59") (name "Net-(U3-B2)") (class "Default")
      (node (ref "R23") (pin "1") (pinfunction "1_1") (pintype "passive"))
      (node (ref "U3") (pin "13") (pinfunction "B2_13") (pintype "bidirectional"))
    )
    (net (code "60") (name "Net-(U3-B3)") (class "Default")
      (node (ref "R25") (pin "1") (pinfunction "1_1") (pintype "passive"))
      (node (ref "R31") (pin "2") (pinfunction "2_2") (pintype "passive"))
      (node (ref "U3") (pin "12") (pinfunction "B3_12") (pintype "bidirectional"))
    )
    (net (code "61") (name "Net-(U3-B4)") (class "Default")
      (node (ref "R27") (pin "1") (pinfunction "1_1") (pintype "passive"))
      (node (ref "R30") (pin "2") (pinfunction "2_2") (pintype "passive"))
      (node (ref "U3") (pin "11") (pinfunction "B4_11") (pintype "bidirectional"))
    )
    (net (code "62") (name "Net-(U3-EN1)") (class "Default")
      (node (ref "R19") (pin "1") (pinfunction "1_1") (pintype "passive"))
      (node (ref "U3") (pin "7") (pinfunction "EN1_7") (pintype "bidirectional"))
    )
    (net (code "63") (name "Net-(U3-EN2)") (class "Default")
      (node (ref "R18") (pin "1") (pinfunction "1_1") (pintype "passive"))
      (node (ref "U3") (pin "10") (pinfunction "EN2_10") (pintype "bidirectional"))
    )
    (net (code "64") (name "Net-(U5-VOC)") (class "Default")
      (node (ref "R43") (pin "1") (pinfunction "1_1") (pintype "passive"))
      (node (ref "R47") (pin "2") (pinfunction "2_2") (pintype "passive"))
      (node (ref "U5") (pin "16") (pinfunction "VOC_16") (pintype "bidirectional"))
    )
    (net (code "65") (name "Net-(U5-VREF)") (class "Default")
      (node (ref "C80") (pin "1") (pinfunction "1_1") (pintype "passive"))
      (node (ref "U5") (pin "13") (pinfunction "VREF_13") (pintype "bidirectional"))
    )
    (net (code "66") (name "Net-(U7-VOC)") (class "Default")
      (node (ref "R52") (pin "1") (pinfunction "1_1") (pintype "passive"))
      (node (ref "R56") (pin "2") (pinfunction "2_2") (pintype "passive"))
      (node (ref "U7") (pin "16") (pinfunction "VOC_16") (pintype "bidirectional"))
    )
    (net (code "67") (name "Net-(U7-VREF)") (class "Default")
      (node (ref "C96") (pin "1") (pinfunction "1_1") (pintype "passive"))
      (node (ref "U7") (pin "13") (pinfunction "VREF_13") (pintype "bidirectional"))
    )
    (net (code "68") (name "Net-(VR2-BOOT)") (class "Default")
      (node (ref "R32") (pin "1") (pinfunction "1_1") (pintype "passive"))
      (node (ref "VR2") (pin "6") (pinfunction "BOOT_6") (pintype "bidirectional"))
    )
    (net (code "69") (name "Net-(VR2-EN)") (class "Default")
      (node (ref "R33") (pin "1") (pinfunction "1_1") (pintype "passive"))
      (node (ref "R35") (pin "2") (pinfunction "2_2") (pintype "passive"))
      (node (ref "VR2") (pin "5") (pinfunction "EN_5") (pintype "bidirectional"))
    )
    (net (code "70") (name "Net-(VR2-FB)") (class "Default")
      (node (ref "R34") (pin "1") (pinfunction "1_1") (pintype "passive"))
      (node (ref "R36") (pin "2") (pinfunction "2_2") (pintype "passive"))
      (node (ref "VR2") (pin "4") (pinfunction "FB_4") (pintype "bidirectional"))
    )
    (net (code "71") (name "Net-(VR2-SW)") (class "Default")
      (node (ref "C39") (pin "2") (pinfunction "2_2") (pintype "passive"))
      (node (ref "L2") (pin "1") (pinfunction "1_1") (pintype "passive"))
      (node (ref "R34") (pin "2") (pinfunction "2_2") (pintype "passive"))
      (node (ref "VR2") (pin "2") (pinfunction "SW_2") (pintype "bidirectional"))
    )
    (net (code "72") (name "PLATE_CURR_AMP") (class "Default")
      (node (ref "R51") (pin "1") (pinfunction "1_1") (pintype "passive"))
      (node (ref "R53") (pin "1") (pinfunction "1_1") (pintype "passive"))
      (node (ref "U6") (pin "3") (pinfunction "VIN_3") (pintype "input"))
    )
    (net (code "73") (name "PLATE_CURR_FAULT") (class "Default")
      (node (ref "TP1") (pin "TP") (pinfunction "TP_TP") (pintype "input"))
      (node (ref "U7") (pin "9") (pinfunction "~{FAULTB}_9") (pintype "bidirectional"))
    )
    (net (code "74") (name "PLATE_CURR_OUT") (class "Default")
      (node (ref "IC2") (pin "1") (pinfunction "+IN_1") (pintype "input"))
      (node (ref "R53") (pin "2") (pinfunction "2_2") (pintype "passive"))
      (node (ref "U7") (pin "12") (pinfunction "VOUT_12") (pintype "bidirectional"))
    )
    (net (code "75") (name "VALVE_-30V") (class "Default")
      (node (ref "U5") (pin "5") (pinfunction "IP-_5") (pintype "bidirectional"))
      (node (ref "U5") (pin "6") (pinfunction "IP-_6") (pintype "bidirectional"))
      (node (ref "U5") (pin "7") (pinfunction "IP-_7") (pintype "bidirectional"))
      (node (ref "U5") (pin "8") (pinfunction "IP-_8") (pintype "bidirectional"))
      (node (ref "X7") (pin "1") (pinfunction "1_1") (pintype "passive"))
    )
    (net (code "76") (name "VALVE_-30V_GEN") (class "Default")
      (node (ref "C31") (pin "2") (pinfunction "2_2") (pintype "passive"))
      (node (ref "C32") (pin "2") (pinfunction "2_2") (pintype "passive"))
      (node (ref "C33") (pin "2") (pinfunction "2_2") (pintype "passive"))
      (node (ref "C34") (pin "2") (pinfunction "2_2") (pintype "passive"))
      (node (ref "D10") (pin "A") (pinfunction "A_A") (pintype "passive"))
      (node (ref "D9") (pin "A") (pinfunction "A_A") (pintype "passive"))
      (node (ref "U5") (pin "1") (pinfunction "IP+_1") (pintype "bidirectional"))
      (node (ref "U5") (pin "2") (pinfunction "IP+_2") (pintype "bidirectional"))
      (node (ref "U5") (pin "3") (pinfunction "IP+_3") (pintype "bidirectional"))
      (node (ref "U5") (pin "4") (pinfunction "IP+_4") (pintype "bidirectional"))
    )
    (net (code "77") (name "VALVE_2.5KV") (class "Default")
      (node (ref "C57") (pin "1") (pinfunction "1_1") (pintype "passive"))
      (node (ref "C58") (pin "1") (pinfunction "1_1") (pintype "passive"))
      (node (ref "C59") (pin "1") (pinfunction "1_1") (pintype "passive"))
      (node (ref "C60") (pin "+VE") (pinfunction "+_+VE") (pintype "passive"))
      (node (ref "D11") (pin "3") (pinfunction "CATHODE_3") (pintype "bidirectional"))
      (node (ref "D12") (pin "3") (pinfunction "CATHODE_3") (pintype "bidirectional"))
      (node (ref "R1") (pin "1") (pinfunction "1_1") (pintype "passive"))
      (node (ref "R37") (pin "2") (pinfunction "2_2") (pintype "passive"))
      (node (ref "R38") (pin "2") (pinfunction "2_2") (pintype "passive"))
      (node (ref "X14") (pin "1") (pinfunction "1_1") (pintype "passive"))
      (node (ref "X14") (pin "2") (pinfunction "2_2") (pintype "passive"))
    )
    (net (code "78") (name "VALVE_5V") (class "Default")
      (node (ref "C11") (pin "1") (pinfunction "1_1") (pintype "passive"))
      (node (ref "C12") (pin "1") (pinfunction "1_1") (pintype "passive"))
      (node (ref "C14") (pin "1") (pinfunction "1_1") (pintype "passive"))
      (node (ref "C16") (pin "1") (pinfunction "1_1") (pintype "passive"))
      (node (ref "C18") (pin "1") (pinfunction "1_1") (pintype "passive"))
      (node (ref "C2") (pin "1") (pinfunction "1_1") (pintype "passive"))
      (node (ref "C20") (pin "1") (pinfunction "1_1") (pintype "passive"))
      (node (ref "C3") (pin "1") (pinfunction "1_1") (pintype "passive"))
      (node (ref "C35") (pin "1") (pinfunction "1_1") (pintype "passive"))
      (node (ref "C36") (pin "1") (pinfunction "1_1") (pintype "passive"))
      (node (ref "C37") (pin "1") (pinfunction "1_1") (pintype "passive"))
      (node (ref "C38") (pin "1") (pinfunction "1_1") (pintype "passive"))
      (node (ref "C5") (pin "1") (pinfunction "1_1") (pintype "passive"))
      (node (ref "C6") (pin "1") (pinfunction "1_1") (pintype "passive"))
      (node (ref "C8") (pin "1") (pinfunction "1_1") (pintype "passive"))
      (node (ref "C9") (pin "1") (pinfunction "1_1") (pintype "passive"))
      (node (ref "D1") (pin "C") (pinfunction "CATHODE_C") (pintype "bidirectional"))
      (node (ref "P2") (pin "1") (pinfunction "1_1") (pintype "passive"))
      (node (ref "P2") (pin "2") (pinfunction "2_2") (pintype "passive"))
      (node (ref "P2") (pin "3") (pinfunction "3_3") (pintype "passive"))
      (node (ref "P2") (pin "4") (pinfunction "4_4") (pintype "passive"))
      (node (ref "P2") (pin "5") (pinfunction "5_5") (pintype "passive"))
      (node (ref "P2") (pin "6") (pinfunction "6_6") (pintype "passive"))
      (node (ref "P2") (pin "7") (pinfunction "7_7") (pintype "passive"))
      (node (ref "P2") (pin "8") (pinfunction "8_8") (pintype "passive"))
      (node (ref "R18") (pin "2") (pinfunction "2_2") (pintype "passive"))
      (node (ref "R5") (pin "2") (pinfunction "2_2") (pintype "passive"))
      (node (ref "U1") (pin "1") (pinfunction "VA_1") (pintype "power_in"))
      (node (ref "U2") (pin "16") (pinfunction "VDD2_16") (pintype "power_in"))
      (node (ref "U3") (pin "16") (pinfunction "VDD2_16") (pintype "power_in"))
      (node (ref "VR1") (pin "+V") (pinfunction "V+_+V") (pintype "passive"))
      (node (ref "X9") (pin "2") (pinfunction "2_2") (pintype "passive"))
    )
    (net (code "79") (name "VALVE_6V3") (class "Default")
      (node (ref "C27") (pin "1") (pinfunction "1_1") (pintype "passive"))
      (node (ref "C28") (pin "1") (pinfunction "1_1") (pintype "passive"))
      (node (ref "C29") (pin "1") (pinfunction "1_1") (pintype "passive"))
      (node (ref "C30") (pin "1") (pinfunction "1_1") (pintype "passive"))
      (node (ref "D3") (pin "C") (pinfunction "C_C") (pintype "passive"))
      (node (ref "D4") (pin "C") (pinfunction "C_C") (pintype "passive"))
      (node (ref "X2") (pin "2") (pinfunction "2_2") (pintype "passive"))
    )
    (net (code "80") (name "VALVE_GND") (class "Default")
      (node (ref "C11") (pin "2") (pinfunction "2_2") (pintype "passive"))
      (node (ref "C12") (pin "2") (pinfunction "2_2") (pintype "passive"))
      (node (ref "C14") (pin "2") (pinfunction "2_2") (pintype "passive"))
      (node (ref "C16") (pin "2") (pinfunction "2_2") (pintype "passive"))
      (node (ref "C18") (pin "2") (pinfunction "2_2") (pintype "passive"))
      (node (ref "C2") (pin "2") (pinfunction "2_2") (pintype "passive"))
      (node (ref "C20") (pin "2") (pinfunction "2_2") (pintype "passive"))
      (node (ref "C27") (pin "2") (pinfunction "2_2") (pintype "passive"))
      (node (ref "C28") (pin "2") (pinfunction "2_2") (pintype "passive"))
      (node (ref "C29") (pin "2") (pinfunction "2_2") (pintype "passive"))
      (node (ref "C3") (pin "2") (pinfunction "2_2") (pintype "passive"))
      (node (ref "C30") (pin "2") (pinfunction "2_2") (pintype "passive"))
      (node (ref "C31") (pin "1") (pinfunction "1_1") (pintype "passive"))
      (node (ref "C32") (pin "1") (pinfunction "1_1") (pintype "passive"))
      (node (ref "C33") (pin "1") (pinfunction "1_1") (pintype "passive"))
      (node (ref "C34") (pin "1") (pinfunction "1_1") (pintype "passive"))
      (node (ref "C35") (pin "2") (pinfunction "2_2") (pintype "passive"))
      (node (ref "C36") (pin "2") (pinfunction "2_2") (pintype "passive"))
      (node (ref "C37") (pin "2") (pinfunction "2_2") (pintype "passive"))
      (node (ref "C38") (pin "2") (pinfunction "2_2") (pintype "passive"))
      (node (ref "C5") (pin "2") (pinfunction "2_2") (pintype "passive"))
      (node (ref "C6") (pin "2") (pinfunction "2_2") (pintype "passive"))
      (node (ref "C8") (pin "2") (pinfunction "2_2") (pintype "passive"))
      (node (ref "C87") (pin "2") (pinfunction "2_2") (pintype "passive"))
      (node (ref "C9") (pin "2") (pinfunction "2_2") (pintype "passive"))
      (node (ref "D2") (pin "A") (pinfunction "ANODE_A") (pintype "bidirectional"))
      (node (ref "D5") (pin "A") (pinfunction "A_A") (pintype "passive"))
      (node (ref "D6") (pin "A") (pinfunction "A_A") (pintype "passive"))
      (node (ref "D7") (pin "C") (pinfunction "C_C") (pintype "passive"))
      (node (ref "D8") (pin "C") (pinfunction "C_C") (pintype "passive"))
      (node (ref "P2") (pin "14") (pinfunction "14_14") (pintype "passive"))
      (node (ref "P2") (pin "15") (pinfunction "15_15") (pintype "passive"))
      (node (ref "P2") (pin "16") (pinfunction "16_16") (pintype "passive"))
      (node (ref "P2") (pin "17") (pinfunction "17_17") (pintype "passive"))
      (node (ref "P2") (pin "18") (pinfunction "18_18") (pintype "passive"))
      (node (ref "P2") (pin "19") (pinfunction "19_19") (pintype "passive"))
      (node (ref "P2") (pin "20") (pinfunction "20_20") (pintype "passive"))
      (node (ref "R15") (pin "1") (pinfunction "1_1") (pintype "passive"))
      (node (ref "R30") (pin "1") (pinfunction "1_1") (pintype "passive"))
      (node (ref "R31") (pin "1") (pinfunction "1_1") (pintype "passive"))
      (node (ref "U1") (pin "2") (pinfunction "GND_2") (pintype "power_in"))
      (node (ref "U2") (pin "15") (pinfunction "GND2_15") (pintype "power_in"))
      (node (ref "U2") (pin "9") (pinfunction "GND2_9") (pintype "power_in"))
      (node (ref "U3") (pin "15") (pinfunction "GND2_15") (pintype "power_in"))
      (node (ref "U3") (pin "9") (pinfunction "GND2_9") (pintype "power_in"))
      (node (ref "U7") (pin "5") (pinfunction "IP-_5") (pintype "bidirectional"))
      (node (ref "U7") (pin "6") (pinfunction "IP-_6") (pintype "bidirectional"))
      (node (ref "U7") (pin "7") (pinfunction "IP-_7") (pintype "bidirectional"))
      (node (ref "U7") (pin "8") (pinfunction "IP-_8") (pintype "bidirectional"))
      (node (ref "VR1") (pin "-V") (pinfunction "V-_-V") (pintype "passive"))
      (node (ref "X17") (pin "1") (pinfunction "1_1") (pintype "passive"))
      (node (ref "X17") (pin "2") (pinfunction "2_2") (pintype "passive"))
      (node (ref "X2") (pin "1") (pinfunction "1_1") (pintype "passive"))
      (node (ref "X7") (pin "2") (pinfunction "2_2") (pintype "passive"))
      (node (ref "X9") (pin "1") (pinfunction "1_1") (pintype "passive"))
    )
    (net (code "81") (name "VALVE_LOW") (class "Default")
      (node (ref "C61") (pin "2") (pinfunction "2_2") (pintype "passive"))
      (node (ref "C62") (pin "2") (pinfunction "2_2") (pintype "passive"))
      (node (ref "C63") (pin "2") (pinfunction "2_2") (pintype "passive"))
      (node (ref "C82") (pin "-VE") (pinfunction "-_-VE") (pintype "passive"))
      (node (ref "C87") (pin "1") (pinfunction "1_1") (pintype "passive"))
      (node (ref "D17") (pin "1") (pinfunction "ANODE_1") (pintype "bidirectional"))
      (node (ref "D18") (pin "1") (pinfunction "ANODE_1") (pintype "bidirectional"))
      (node (ref "R39") (pin "1") (pinfunction "1_1") (pintype "passive"))
      (node (ref "R50") (pin "1") (pinfunction "1_1") (pintype "passive"))
      (node (ref "U7") (pin "1") (pinfunction "IP+_1") (pintype "bidirectional"))
      (node (ref "U7") (pin "2") (pinfunction "IP+_2") (pintype "bidirectional"))
      (node (ref "U7") (pin "3") (pinfunction "IP+_3") (pintype "bidirectional"))
      (node (ref "U7") (pin "4") (pinfunction "IP+_4") (pintype "bidirectional"))
    )
    (net (code "82") (name "VALVE_MISO") (class "Default")
      (node (ref "P1") (pin "5") (pinfunction "5_5") (pintype "passive"))
      (node (ref "R16") (pin "1") (pinfunction "1_1") (pintype "passive"))
      (node (ref "U4") (pin "5") (pinfunction "SDATA_5") (pintype "output"))
      (node (ref "U6") (pin "5") (pinfunction "SDATA_5") (pintype "output"))
    )
    (net (code "83") (name "VALVE_MOSI") (class "Default")
      (node (ref "P1") (pin "7") (pinfunction "7_7") (pintype "passive"))
      (node (ref "R13") (pin "1") (pinfunction "1_1") (pintype "passive"))
    )
    (net (code "84") (name "VALVE_SCLK") (class "Default")
      (node (ref "P1") (pin "8") (pinfunction "8_8") (pintype "passive"))
      (node (ref "R11") (pin "1") (pinfunction "1_1") (pintype "passive"))
      (node (ref "U4") (pin "4") (pinfunction "SCLK_4") (pintype "input"))
      (node (ref "U6") (pin "4") (pinfunction "SCLK_4") (pintype "input"))
    )
    (net (code "85") (name "V_MISO") (class "Default")
      (node (ref "P2") (pin "11") (pinfunction "11_11") (pintype "passive"))
      (node (ref "R17") (pin "2") (pinfunction "2_2") (pintype "passive"))
      (node (ref "U1") (pin "5") (pinfunction "SDATA_5") (pintype "output"))
    )
    (net (code "86") (name "V_MOSI") (class "Default")
      (node (ref "P2") (pin "13") (pinfunction "13_13") (pintype "passive"))
      (node (ref "R14") (pin "2") (pinfunction "2_2") (pintype "passive"))
    )
    (net (code "87") (name "V_SCLK") (class "Default")
      (node (ref "P2") (pin "12") (pinfunction "12_12") (pintype "passive"))
      (node (ref "R12") (pin "2") (pinfunction "2_2") (pintype "passive"))
      (node (ref "U1") (pin "4") (pinfunction "SCLK_4") (pintype "input"))
    )
    (net (code "88") (name "unconnected-(R25-Pad2)") (class "Default")
      (node (ref "R25") (pin "2") (pinfunction "2_2") (pintype "passive"))
    )
    (net (code "89") (name "unconnected-(R27-Pad2)") (class "Default")
      (node (ref "R27") (pin "2") (pinfunction "2_2") (pintype "passive"))
    )
    (net (code "90") (name "~{VALVE_GRID_CUR_SS}") (class "Default")
      (node (ref "P1") (pin "1") (pinfunction "1_1") (pintype "passive"))
      (node (ref "U4") (pin "6") (pinfunction "~{CS}_6") (pintype "passive"))
    )
    (net (code "91") (name "~{VALVE_OUT_FWD_SS}") (class "Default")
      (node (ref "P1") (pin "3") (pinfunction "3_3") (pintype "passive"))
      (node (ref "R20") (pin "1") (pinfunction "1_1") (pintype "passive"))
    )
    (net (code "92") (name "~{VALVE_OUT_RVS_SS}") (class "Default")
      (node (ref "P1") (pin "4") (pinfunction "4_4") (pintype "passive"))
      (node (ref "R22") (pin "1") (pinfunction "1_1") (pintype "passive"))
    )
    (net (code "93") (name "~{VALVE_PLATE_CUR_SS}") (class "Default")
      (node (ref "P1") (pin "2") (pinfunction "2_2") (pintype "passive"))
      (node (ref "U6") (pin "6") (pinfunction "~{CS}_6") (pintype "passive"))
    )
    (net (code "94") (name "~{VALVE_VOLT_SS}") (class "Default")
      (node (ref "P1") (pin "6") (pinfunction "6_6") (pintype "passive"))
      (node (ref "R9") (pin "1") (pinfunction "1_1") (pintype "passive"))
    )
    (net (code "95") (name "~{V_OUT_FWD_SS}") (class "Default")
      (node (ref "P2") (pin "9") (pinfunction "9_9") (pintype "passive"))
      (node (ref "R21") (pin "2") (pinfunction "2_2") (pintype "passive"))
    )
    (net (code "96") (name "~{V_OUT_RVS_SS}") (class "Default")
      (node (ref "P2") (pin "10") (pinfunction "10_10") (pintype "passive"))
      (node (ref "R23") (pin "2") (pinfunction "2_2") (pintype "passive"))
    )
  )
)
